# axiom_beta_sensor_cmv12000_v0_15_tht.net
KiCad netlist of a schematic drawn in EAGLE
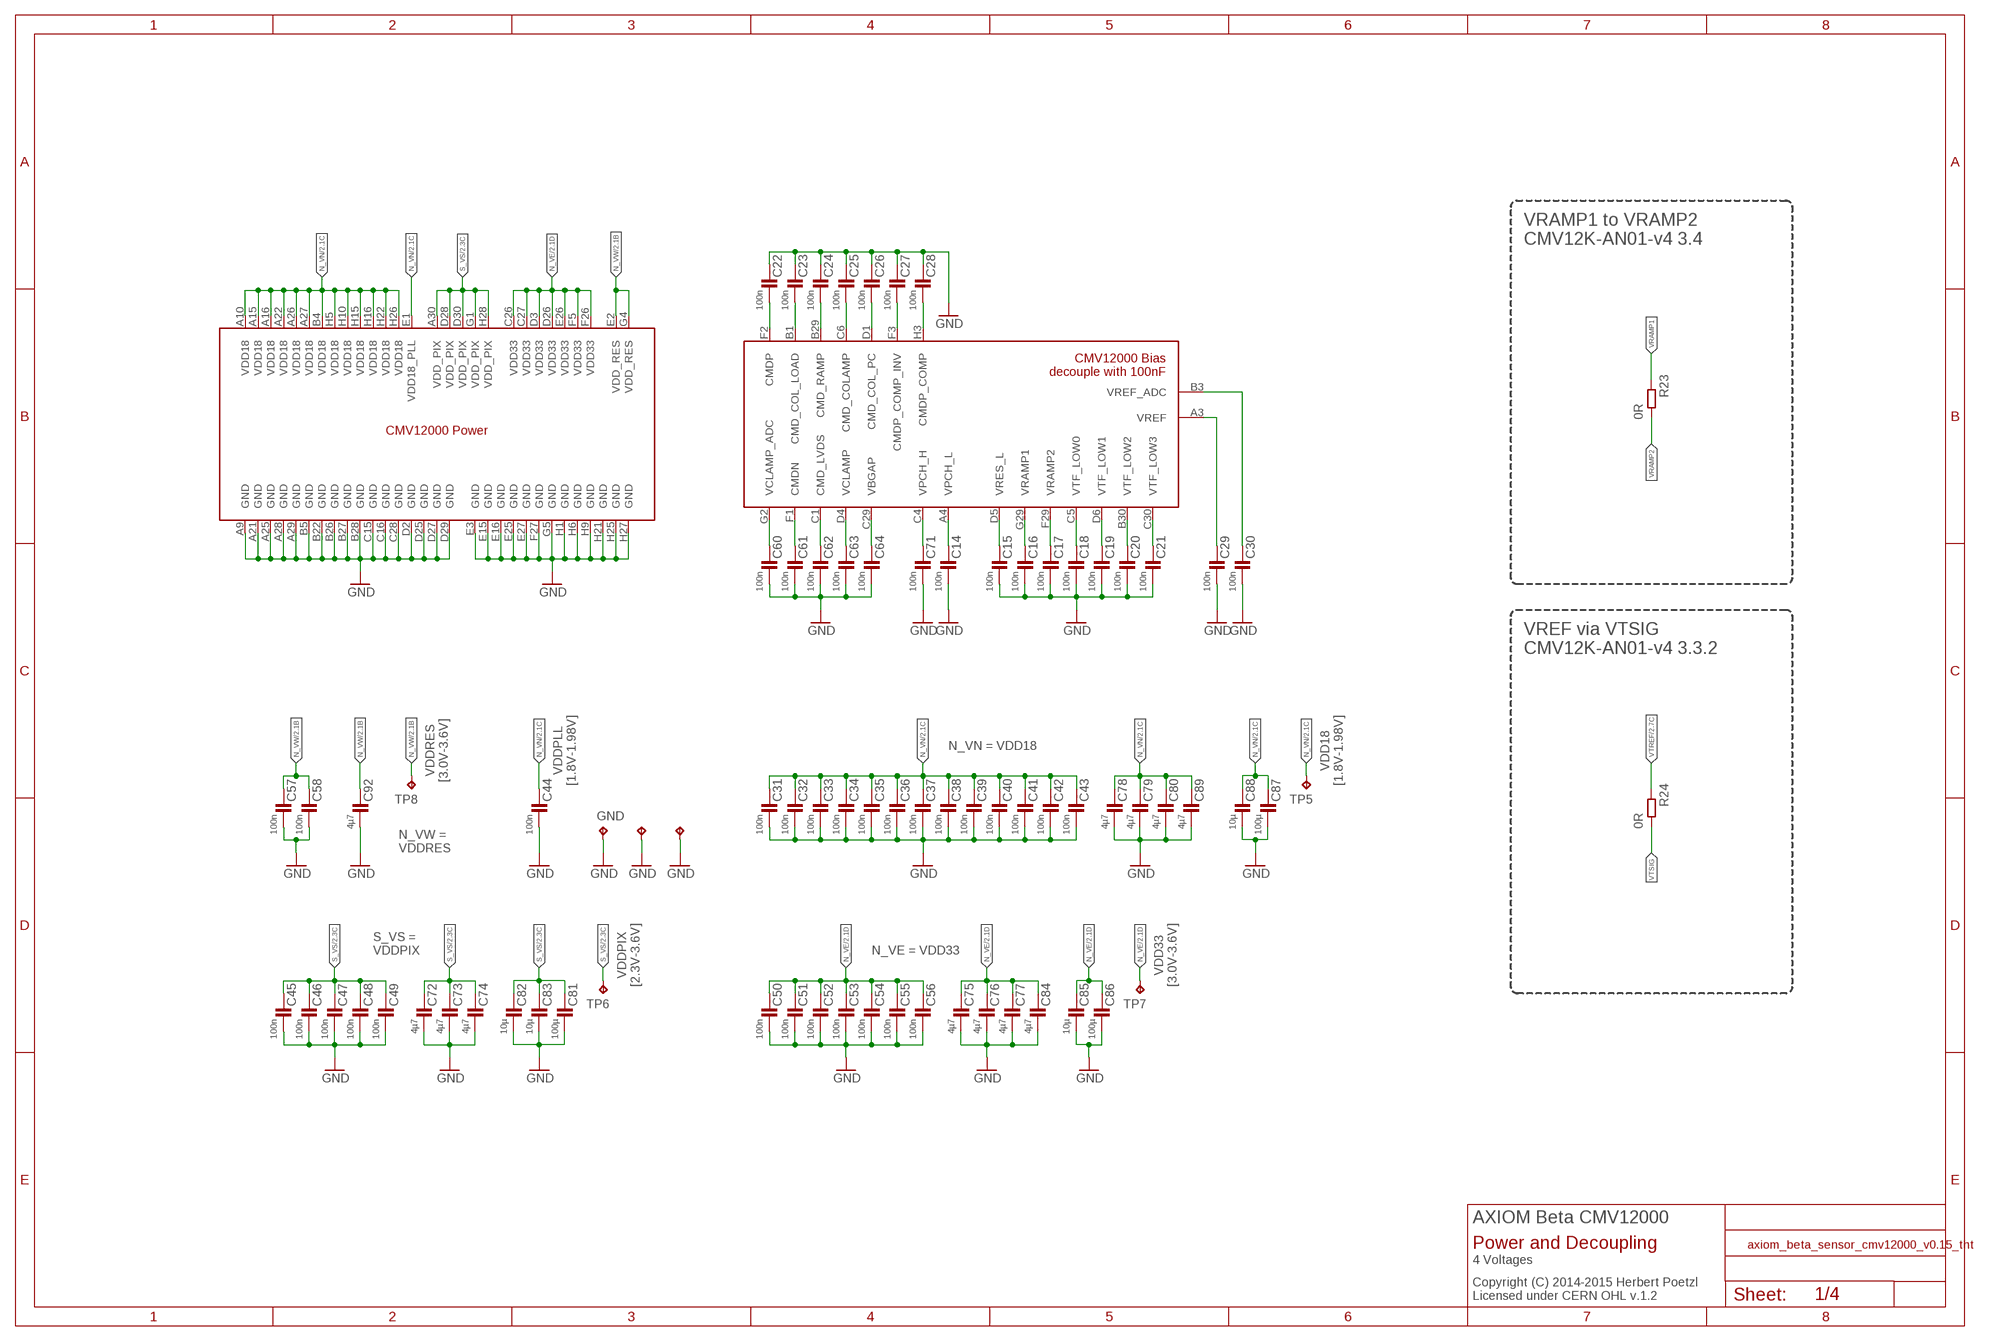
[diagram p0: schematic, sheet 1]
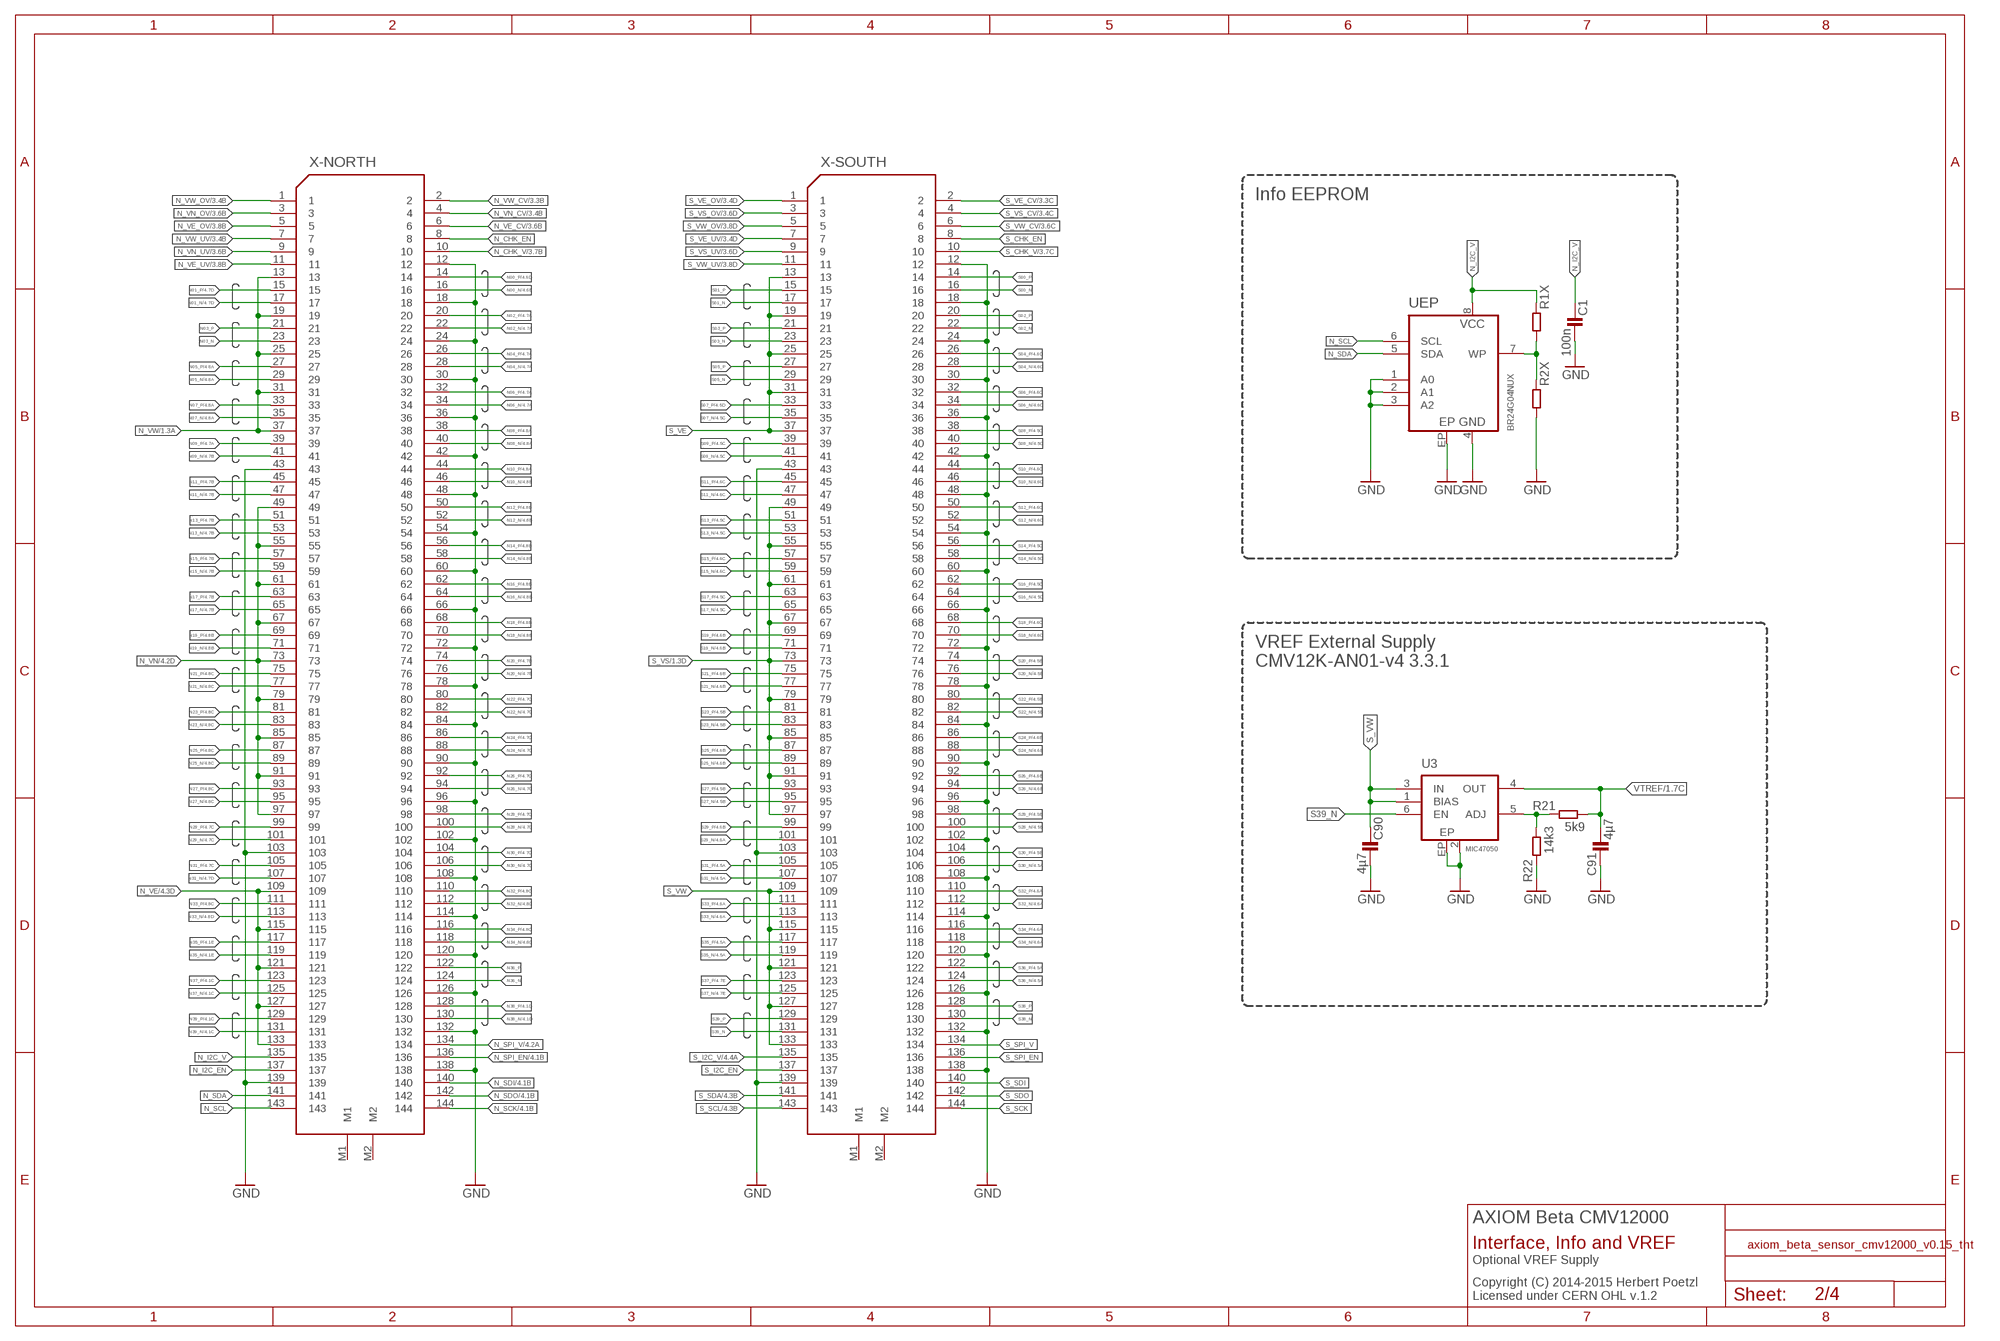
[diagram p1: schematic, sheet 2]
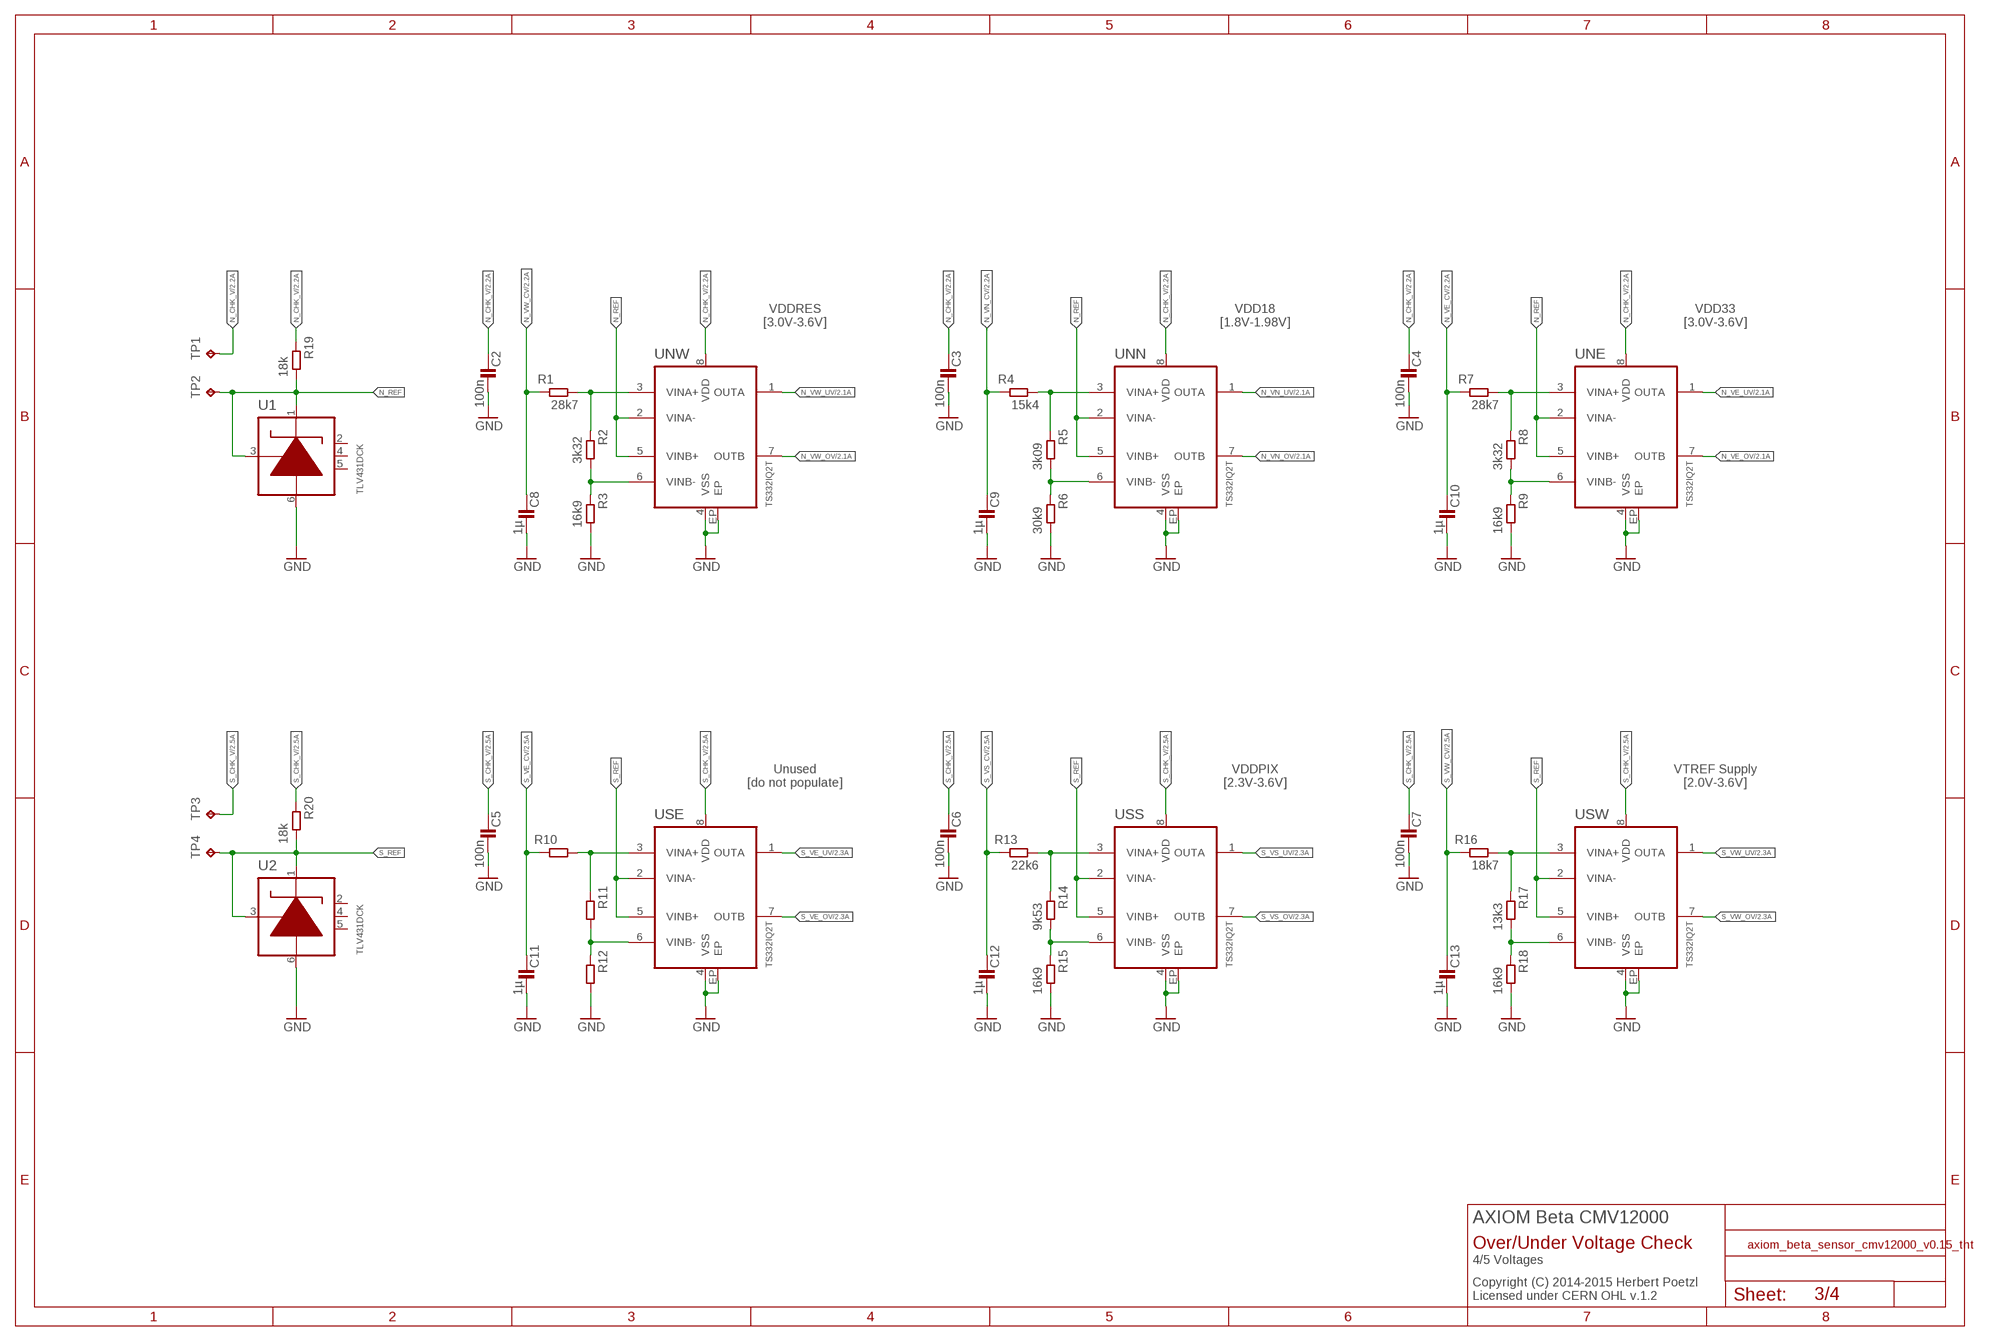
[diagram p2: schematic, sheet 3]
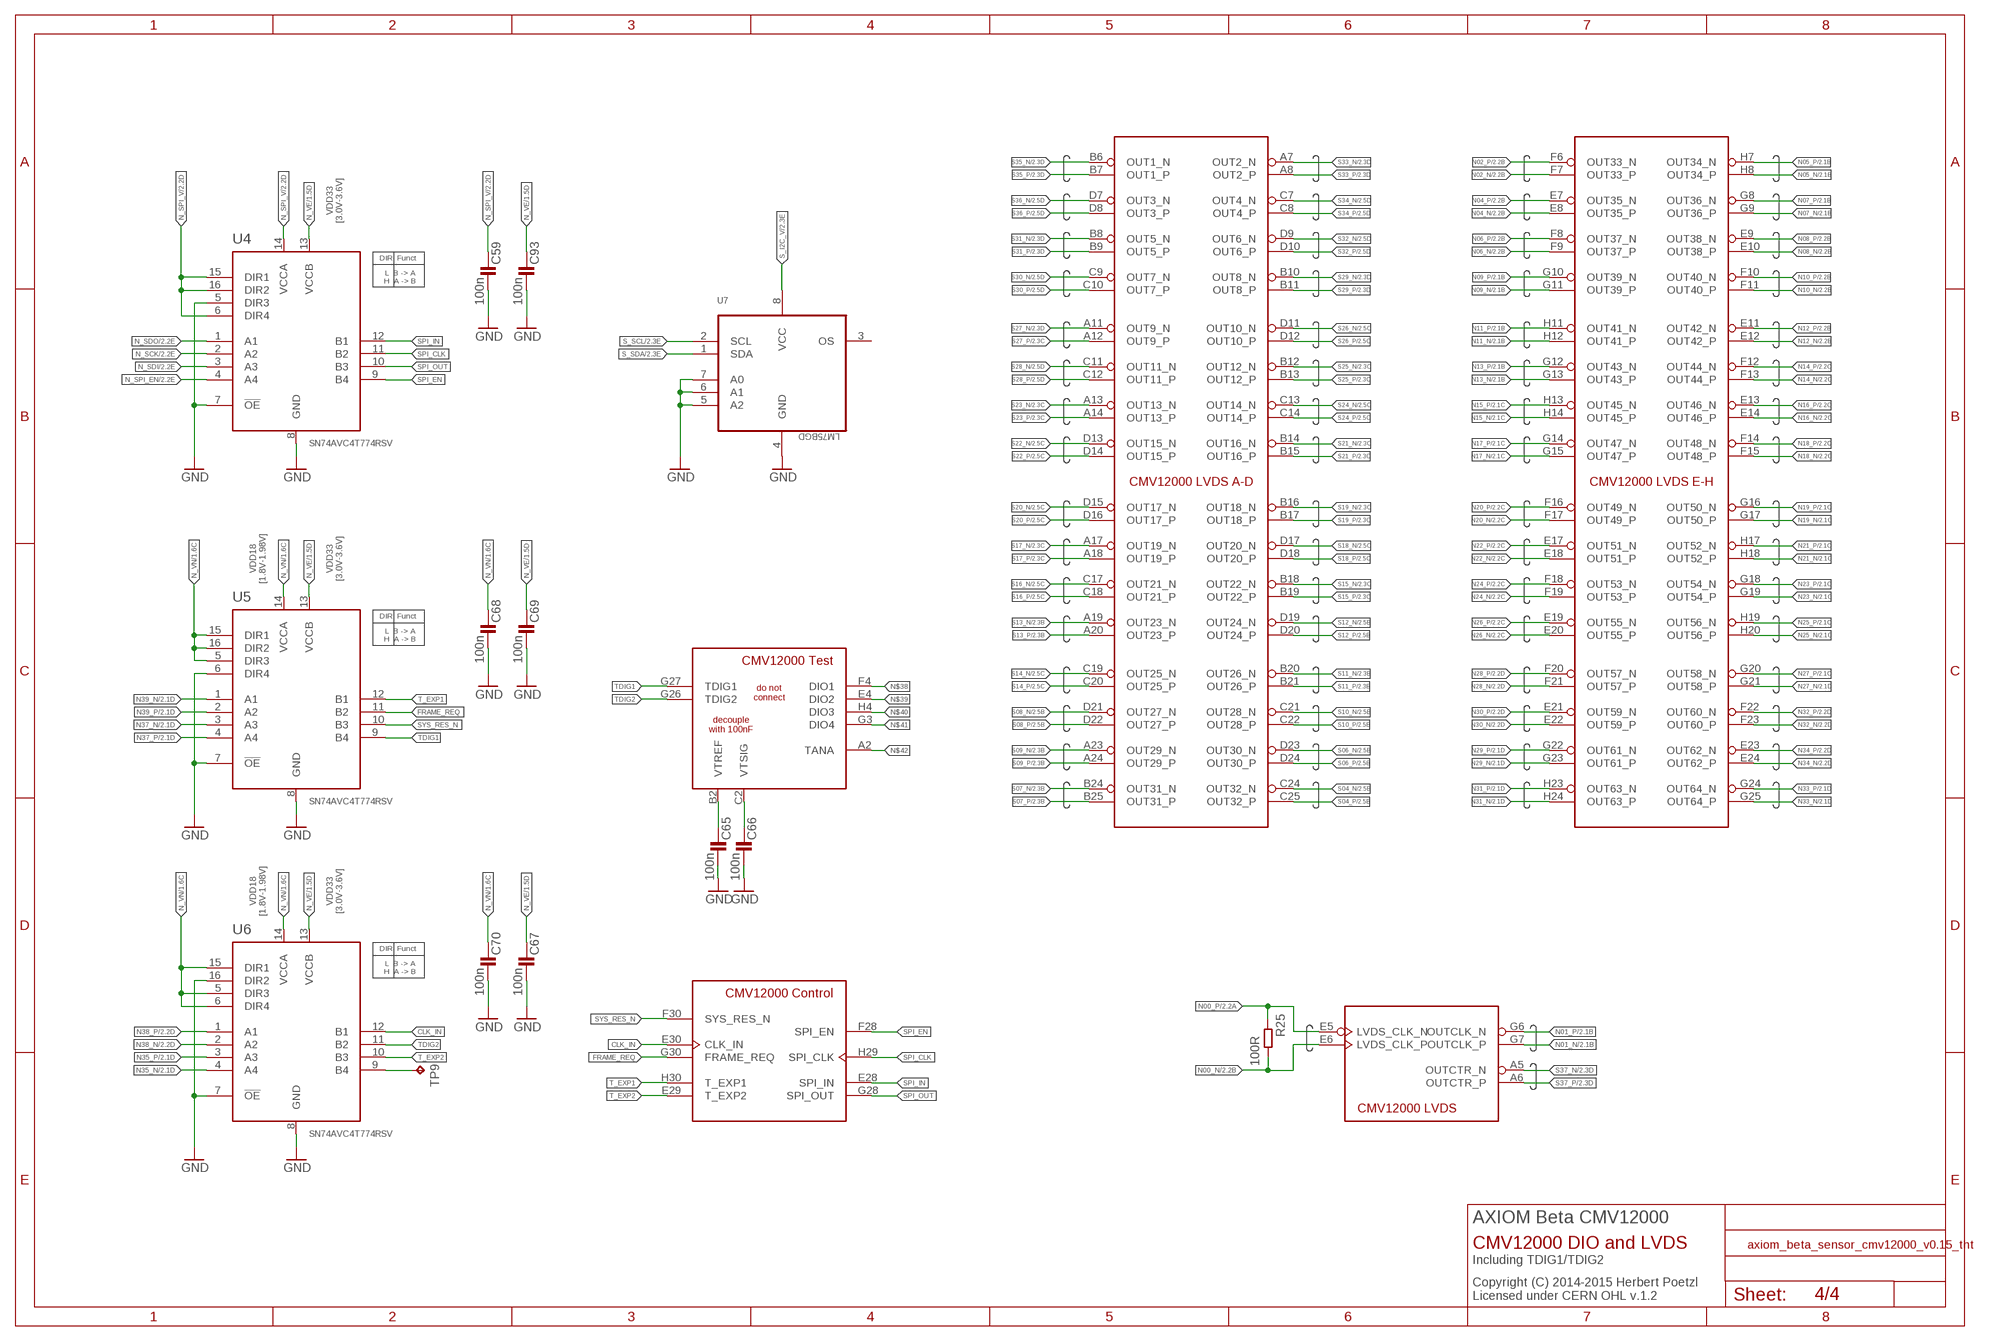
[diagram p3: schematic, sheet 4]

(export (version "E")
  (design (tool "Eeschema 10.0.6"))
  (components
    (comp (ref "C59")
      (value "100n")
      (footprint "eagle-import:0402-C")
      (libsource (lib "eagle-import") (part "C0402-C"))
    )
    (comp (ref "C65")
      (value "100n")
      (footprint "eagle-import:0402-C")
      (libsource (lib "eagle-import") (part "C0402-C"))
    )
    (comp (ref "C66")
      (value "100n")
      (footprint "eagle-import:0402-C")
      (libsource (lib "eagle-import") (part "C0402-C"))
    )
    (comp (ref "C67")
      (value "100n")
      (footprint "eagle-import:0402-C")
      (libsource (lib "eagle-import") (part "C0402-C"))
    )
    (comp (ref "C68")
      (value "100n")
      (footprint "eagle-import:0402-C")
      (libsource (lib "eagle-import") (part "C0402-C"))
    )
    (comp (ref "C69")
      (value "100n")
      (footprint "eagle-import:0402-C")
      (libsource (lib "eagle-import") (part "C0402-C"))
    )
    (comp (ref "C70")
      (value "100n")
      (footprint "eagle-import:0402-C")
      (libsource (lib "eagle-import") (part "C0402-C"))
    )
    (comp (ref "C93")
      (value "100n")
      (footprint "eagle-import:0402-C")
      (libsource (lib "eagle-import") (part "C0402-C"))
    )
    (comp (ref "R25")
      (value "100R")
      (footprint "eagle-import:0402-C")
      (libsource (lib "eagle-import") (part "R0402-C"))
    )
    (comp (ref "SENSOR")
      (value "CMV12000ANDON")
      (footprint "eagle-import:10-30-07-237-400T4")
      (libsource (lib "eagle-import") (part "CMV12000ANDON"))
    )
    (comp (ref "TP9")
      (value "TPTP10R")
      (footprint "eagle-import:TP10R")
      (libsource (lib "eagle-import") (part "TPTP10R"))
    )
    (comp (ref "U4")
      (value "SN74AVC4T774RSV")
      (footprint "eagle-import:QFN40P185X265X55-16N")
      (libsource (lib "eagle-import") (part "SN74AVC4T774RSV"))
    )
    (comp (ref "U5")
      (value "SN74AVC4T774RSV")
      (footprint "eagle-import:QFN40P185X265X55-16N")
      (libsource (lib "eagle-import") (part "SN74AVC4T774RSV"))
    )
    (comp (ref "U6")
      (value "SN74AVC4T774RSV")
      (footprint "eagle-import:QFN40P185X265X55-16N")
      (libsource (lib "eagle-import") (part "SN74AVC4T774RSV"))
    )
    (comp (ref "U7")
      (value "LM75BGD")
      (footprint "eagle-import:SOT996-2_3")
      (libsource (lib "eagle-import") (part "LM75BGD"))
    )
    (comp (ref "C1")
      (value "100n")
      (footprint "eagle-import:0402-C")
      (libsource (lib "eagle-import") (part "C0402-C"))
    )
    (comp (ref "C90")
      (value "4µ7")
      (footprint "eagle-import:0402-C")
      (libsource (lib "eagle-import") (part "C0402-C"))
    )
    (comp (ref "C91")
      (value "4µ7")
      (footprint "eagle-import:0402-C")
      (libsource (lib "eagle-import") (part "C0402-C"))
    )
    (comp (ref "R1X")
      (value "R0402-C")
      (footprint "eagle-import:0402-C")
      (libsource (lib "eagle-import") (part "R0402-C"))
    )
    (comp (ref "R2X")
      (value "R0402-C")
      (footprint "eagle-import:0402-C")
      (libsource (lib "eagle-import") (part "R0402-C"))
    )
    (comp (ref "R21")
      (value "5k9")
      (footprint "eagle-import:0402-C")
      (libsource (lib "eagle-import") (part "R0402-C"))
    )
    (comp (ref "R22")
      (value "14k3")
      (footprint "eagle-import:0402-C")
      (libsource (lib "eagle-import") (part "R0402-C"))
    )
    (comp (ref "U3")
      (value "MIC47050")
      (footprint "eagle-import:MLF-6")
      (libsource (lib "eagle-import") (part "MIC47050-ADJ"))
    )
    (comp (ref "UEP")
      (value "BR24G04NUX")
      (footprint "eagle-import:DFN200X300X100-9N")
      (libsource (lib "eagle-import") (part "BR24G04NUX"))
    )
    (comp (ref "X-NORTH")
      (value "FX10-144P")
      (footprint "eagle-import:FX10A-144P")
      (libsource (lib "eagle-import") (part "FX10-144P"))
    )
    (comp (ref "X-SOUTH")
      (value "FX10-144P")
      (footprint "eagle-import:FX10A-144P")
      (libsource (lib "eagle-import") (part "FX10-144P"))
    )
    (comp (ref "C2")
      (value "100n")
      (footprint "eagle-import:0402-C")
      (libsource (lib "eagle-import") (part "C0402-C"))
    )
    (comp (ref "C3")
      (value "100n")
      (footprint "eagle-import:0402-C")
      (libsource (lib "eagle-import") (part "C0402-C"))
    )
    (comp (ref "C4")
      (value "100n")
      (footprint "eagle-import:0402-C")
      (libsource (lib "eagle-import") (part "C0402-C"))
    )
    (comp (ref "C5")
      (value "100n")
      (footprint "eagle-import:0402-C")
      (libsource (lib "eagle-import") (part "C0402-C"))
    )
    (comp (ref "C6")
      (value "100n")
      (footprint "eagle-import:0402-C")
      (libsource (lib "eagle-import") (part "C0402-C"))
    )
    (comp (ref "C7")
      (value "100n")
      (footprint "eagle-import:0402-C")
      (libsource (lib "eagle-import") (part "C0402-C"))
    )
    (comp (ref "C8")
      (value "1µ")
      (footprint "eagle-import:0402-C")
      (libsource (lib "eagle-import") (part "C0402-C"))
    )
    (comp (ref "C9")
      (value "1µ")
      (footprint "eagle-import:0402-C")
      (libsource (lib "eagle-import") (part "C0402-C"))
    )
    (comp (ref "C10")
      (value "1µ")
      (footprint "eagle-import:0402-C")
      (libsource (lib "eagle-import") (part "C0402-C"))
    )
    (comp (ref "C11")
      (value "1µ")
      (footprint "eagle-import:0402-C")
      (libsource (lib "eagle-import") (part "C0402-C"))
    )
    (comp (ref "C12")
      (value "1µ")
      (footprint "eagle-import:0402-C")
      (libsource (lib "eagle-import") (part "C0402-C"))
    )
    (comp (ref "C13")
      (value "1µ")
      (footprint "eagle-import:0402-C")
      (libsource (lib "eagle-import") (part "C0402-C"))
    )
    (comp (ref "R1")
      (value "28k7")
      (footprint "eagle-import:0402-C")
      (libsource (lib "eagle-import") (part "R0402-C"))
    )
    (comp (ref "R2")
      (value "3k32")
      (footprint "eagle-import:0402-C")
      (libsource (lib "eagle-import") (part "R0402-C"))
    )
    (comp (ref "R3")
      (value "16k9")
      (footprint "eagle-import:0402-C")
      (libsource (lib "eagle-import") (part "R0402-C"))
    )
    (comp (ref "R4")
      (value "15k4")
      (footprint "eagle-import:0402-C")
      (libsource (lib "eagle-import") (part "R0402-C"))
    )
    (comp (ref "R5")
      (value "3k09")
      (footprint "eagle-import:0402-C")
      (libsource (lib "eagle-import") (part "R0402-C"))
    )
    (comp (ref "R6")
      (value "30k9")
      (footprint "eagle-import:0402-C")
      (libsource (lib "eagle-import") (part "R0402-C"))
    )
    (comp (ref "R7")
      (value "28k7")
      (footprint "eagle-import:0402-C")
      (libsource (lib "eagle-import") (part "R0402-C"))
    )
    (comp (ref "R8")
      (value "3k32")
      (footprint "eagle-import:0402-C")
      (libsource (lib "eagle-import") (part "R0402-C"))
    )
    (comp (ref "R9")
      (value "16k9")
      (footprint "eagle-import:0402-C")
      (libsource (lib "eagle-import") (part "R0402-C"))
    )
    (comp (ref "R10")
      (value "R0402-C")
      (footprint "eagle-import:0402-C")
      (libsource (lib "eagle-import") (part "R0402-C"))
    )
    (comp (ref "R11")
      (value "R0402-C")
      (footprint "eagle-import:0402-C")
      (libsource (lib "eagle-import") (part "R0402-C"))
    )
    (comp (ref "R12")
      (value "R0402-C")
      (footprint "eagle-import:0402-C")
      (libsource (lib "eagle-import") (part "R0402-C"))
    )
    (comp (ref "R13")
      (value "22k6")
      (footprint "eagle-import:0402-C")
      (libsource (lib "eagle-import") (part "R0402-C"))
    )
    (comp (ref "R14")
      (value "9k53")
      (footprint "eagle-import:0402-C")
      (libsource (lib "eagle-import") (part "R0402-C"))
    )
    (comp (ref "R15")
      (value "16k9")
      (footprint "eagle-import:0402-C")
      (libsource (lib "eagle-import") (part "R0402-C"))
    )
    (comp (ref "R16")
      (value "18k7")
      (footprint "eagle-import:0402-C")
      (libsource (lib "eagle-import") (part "R0402-C"))
    )
    (comp (ref "R17")
      (value "13k3")
      (footprint "eagle-import:0402-C")
      (libsource (lib "eagle-import") (part "R0402-C"))
    )
    (comp (ref "R18")
      (value "16k9")
      (footprint "eagle-import:0402-C")
      (libsource (lib "eagle-import") (part "R0402-C"))
    )
    (comp (ref "R19")
      (value "18k")
      (footprint "eagle-import:0402-C")
      (libsource (lib "eagle-import") (part "R0402-C"))
    )
    (comp (ref "R20")
      (value "18k")
      (footprint "eagle-import:0402-C")
      (libsource (lib "eagle-import") (part "R0402-C"))
    )
    (comp (ref "TP1")
      (value "TPTP10R")
      (footprint "eagle-import:TP10R")
      (libsource (lib "eagle-import") (part "TPTP10R"))
    )
    (comp (ref "TP2")
      (value "TPTP10R")
      (footprint "eagle-import:TP10R")
      (libsource (lib "eagle-import") (part "TPTP10R"))
    )
    (comp (ref "TP3")
      (value "TPTP10R")
      (footprint "eagle-import:TP10R")
      (libsource (lib "eagle-import") (part "TPTP10R"))
    )
    (comp (ref "TP4")
      (value "TPTP10R")
      (footprint "eagle-import:TP10R")
      (libsource (lib "eagle-import") (part "TPTP10R"))
    )
    (comp (ref "U1")
      (value "TLV431DCK")
      (footprint "eagle-import:SOT65P210X110-6N")
      (libsource (lib "eagle-import") (part "TLV431DCK"))
    )
    (comp (ref "U2")
      (value "TLV431DCK")
      (footprint "eagle-import:SOT65P210X110-6N")
      (libsource (lib "eagle-import") (part "TLV431DCK"))
    )
    (comp (ref "UNE")
      (value "TS332IQ2T")
      (footprint "eagle-import:DFN200X200X100-9N")
      (libsource (lib "eagle-import") (part "TS332IQ2T"))
    )
    (comp (ref "UNN")
      (value "TS332IQ2T")
      (footprint "eagle-import:DFN200X200X100-9N")
      (libsource (lib "eagle-import") (part "TS332IQ2T"))
    )
    (comp (ref "UNW")
      (value "TS332IQ2T")
      (footprint "eagle-import:DFN200X200X100-9N")
      (libsource (lib "eagle-import") (part "TS332IQ2T"))
    )
    (comp (ref "USE")
      (value "TS332IQ2T")
      (footprint "eagle-import:DFN200X200X100-9N")
      (libsource (lib "eagle-import") (part "TS332IQ2T"))
    )
    (comp (ref "USS")
      (value "TS332IQ2T")
      (footprint "eagle-import:DFN200X200X100-9N")
      (libsource (lib "eagle-import") (part "TS332IQ2T"))
    )
    (comp (ref "USW")
      (value "TS332IQ2T")
      (footprint "eagle-import:DFN200X200X100-9N")
      (libsource (lib "eagle-import") (part "TS332IQ2T"))
    )
    (comp (ref "C14")
      (value "100n")
      (footprint "eagle-import:0402-C")
      (libsource (lib "eagle-import") (part "C0402-C"))
    )
    (comp (ref "C15")
      (value "100n")
      (footprint "eagle-import:0402-C")
      (libsource (lib "eagle-import") (part "C0402-C"))
    )
    (comp (ref "C16")
      (value "100n")
      (footprint "eagle-import:0402-C")
      (libsource (lib "eagle-import") (part "C0402-C"))
    )
    (comp (ref "C17")
      (value "100n")
      (footprint "eagle-import:0402-C")
      (libsource (lib "eagle-import") (part "C0402-C"))
    )
    (comp (ref "C18")
      (value "100n")
      (footprint "eagle-import:0402-C")
      (libsource (lib "eagle-import") (part "C0402-C"))
    )
    (comp (ref "C19")
      (value "100n")
      (footprint "eagle-import:0402-C")
      (libsource (lib "eagle-import") (part "C0402-C"))
    )
    (comp (ref "C20")
      (value "100n")
      (footprint "eagle-import:0402-C")
      (libsource (lib "eagle-import") (part "C0402-C"))
    )
    (comp (ref "C21")
      (value "100n")
      (footprint "eagle-import:0402-C")
      (libsource (lib "eagle-import") (part "C0402-C"))
    )
    (comp (ref "C22")
      (value "100n")
      (footprint "eagle-import:0402-C")
      (libsource (lib "eagle-import") (part "C0402-C"))
    )
    (comp (ref "C23")
      (value "100n")
      (footprint "eagle-import:0402-C")
      (libsource (lib "eagle-import") (part "C0402-C"))
    )
    (comp (ref "C24")
      (value "100n")
      (footprint "eagle-import:0402-C")
      (libsource (lib "eagle-import") (part "C0402-C"))
    )
    (comp (ref "C25")
      (value "100n")
      (footprint "eagle-import:0402-C")
      (libsource (lib "eagle-import") (part "C0402-C"))
    )
    (comp (ref "C26")
      (value "100n")
      (footprint "eagle-import:0402-C")
      (libsource (lib "eagle-import") (part "C0402-C"))
    )
    (comp (ref "C27")
      (value "100n")
      (footprint "eagle-import:0402-C")
      (libsource (lib "eagle-import") (part "C0402-C"))
    )
    (comp (ref "C28")
      (value "100n")
      (footprint "eagle-import:0402-C")
      (libsource (lib "eagle-import") (part "C0402-C"))
    )
    (comp (ref "C29")
      (value "100n")
      (footprint "eagle-import:0402-C")
      (libsource (lib "eagle-import") (part "C0402-C"))
    )
    (comp (ref "C30")
      (value "100n")
      (footprint "eagle-import:0402-C")
      (libsource (lib "eagle-import") (part "C0402-C"))
    )
    (comp (ref "C31")
      (value "100n")
      (footprint "eagle-import:0402-C")
      (libsource (lib "eagle-import") (part "C0402-C"))
    )
    (comp (ref "C32")
      (value "100n")
      (footprint "eagle-import:0402-C")
      (libsource (lib "eagle-import") (part "C0402-C"))
    )
    (comp (ref "C33")
      (value "100n")
      (footprint "eagle-import:0402-C")
      (libsource (lib "eagle-import") (part "C0402-C"))
    )
    (comp (ref "C34")
      (value "100n")
      (footprint "eagle-import:0402-C")
      (libsource (lib "eagle-import") (part "C0402-C"))
    )
    (comp (ref "C35")
      (value "100n")
      (footprint "eagle-import:0402-C")
      (libsource (lib "eagle-import") (part "C0402-C"))
    )
    (comp (ref "C36")
      (value "100n")
      (footprint "eagle-import:0402-C")
      (libsource (lib "eagle-import") (part "C0402-C"))
    )
    (comp (ref "C37")
      (value "100n")
      (footprint "eagle-import:0402-C")
      (libsource (lib "eagle-import") (part "C0402-C"))
    )
    (comp (ref "C38")
      (value "100n")
      (footprint "eagle-import:0402-C")
      (libsource (lib "eagle-import") (part "C0402-C"))
    )
    (comp (ref "C39")
      (value "100n")
      (footprint "eagle-import:0402-C")
      (libsource (lib "eagle-import") (part "C0402-C"))
    )
    (comp (ref "C40")
      (value "100n")
      (footprint "eagle-import:0402-C")
      (libsource (lib "eagle-import") (part "C0402-C"))
    )
    (comp (ref "C41")
      (value "100n")
      (footprint "eagle-import:0402-C")
      (libsource (lib "eagle-import") (part "C0402-C"))
    )
    (comp (ref "C42")
      (value "100n")
      (footprint "eagle-import:0402-C")
      (libsource (lib "eagle-import") (part "C0402-C"))
    )
    (comp (ref "C43")
      (value "100n")
      (footprint "eagle-import:0402-C")
      (libsource (lib "eagle-import") (part "C0402-C"))
    )
    (comp (ref "C44")
      (value "100n")
      (footprint "eagle-import:0402-C")
      (libsource (lib "eagle-import") (part "C0402-C"))
    )
    (comp (ref "C45")
      (value "100n")
      (footprint "eagle-import:0402-C")
      (libsource (lib "eagle-import") (part "C0402-C"))
    )
    (comp (ref "C46")
      (value "100n")
      (footprint "eagle-import:0402-C")
      (libsource (lib "eagle-import") (part "C0402-C"))
    )
    (comp (ref "C47")
      (value "100n")
      (footprint "eagle-import:0402-C")
      (libsource (lib "eagle-import") (part "C0402-C"))
    )
    (comp (ref "C48")
      (value "100n")
      (footprint "eagle-import:0402-C")
      (libsource (lib "eagle-import") (part "C0402-C"))
    )
    (comp (ref "C49")
      (value "100n")
      (footprint "eagle-import:0402-C")
      (libsource (lib "eagle-import") (part "C0402-C"))
    )
    (comp (ref "C50")
      (value "100n")
      (footprint "eagle-import:0402-C")
      (libsource (lib "eagle-import") (part "C0402-C"))
    )
    (comp (ref "C51")
      (value "100n")
      (footprint "eagle-import:0402-C")
      (libsource (lib "eagle-import") (part "C0402-C"))
    )
    (comp (ref "C52")
      (value "100n")
      (footprint "eagle-import:0402-C")
      (libsource (lib "eagle-import") (part "C0402-C"))
    )
    (comp (ref "C53")
      (value "100n")
      (footprint "eagle-import:0402-C")
      (libsource (lib "eagle-import") (part "C0402-C"))
    )
    (comp (ref "C54")
      (value "100n")
      (footprint "eagle-import:0402-C")
      (libsource (lib "eagle-import") (part "C0402-C"))
    )
    (comp (ref "C55")
      (value "100n")
      (footprint "eagle-import:0402-C")
      (libsource (lib "eagle-import") (part "C0402-C"))
    )
    (comp (ref "C56")
      (value "100n")
      (footprint "eagle-import:0402-C")
      (libsource (lib "eagle-import") (part "C0402-C"))
    )
    (comp (ref "C57")
      (value "100n")
      (footprint "eagle-import:0402-C")
      (libsource (lib "eagle-import") (part "C0402-C"))
    )
    (comp (ref "C58")
      (value "100n")
      (footprint "eagle-import:0402-C")
      (libsource (lib "eagle-import") (part "C0402-C"))
    )
    (comp (ref "C60")
      (value "100n")
      (footprint "eagle-import:0402-C")
      (libsource (lib "eagle-import") (part "C0402-C"))
    )
    (comp (ref "C61")
      (value "100n")
      (footprint "eagle-import:0402-C")
      (libsource (lib "eagle-import") (part "C0402-C"))
    )
    (comp (ref "C62")
      (value "100n")
      (footprint "eagle-import:0402-C")
      (libsource (lib "eagle-import") (part "C0402-C"))
    )
    (comp (ref "C63")
      (value "100n")
      (footprint "eagle-import:0402-C")
      (libsource (lib "eagle-import") (part "C0402-C"))
    )
    (comp (ref "C64")
      (value "100n")
      (footprint "eagle-import:0402-C")
      (libsource (lib "eagle-import") (part "C0402-C"))
    )
    (comp (ref "C71")
      (value "100n")
      (footprint "eagle-import:0402-C")
      (libsource (lib "eagle-import") (part "C0402-C"))
    )
    (comp (ref "C72")
      (value "4µ7")
      (footprint "eagle-import:0402-B")
      (libsource (lib "eagle-import") (part "C0402-B"))
    )
    (comp (ref "C73")
      (value "4µ7")
      (footprint "eagle-import:0402-C")
      (libsource (lib "eagle-import") (part "C0402-C"))
    )
    (comp (ref "C74")
      (value "4µ7")
      (footprint "eagle-import:0402-C")
      (libsource (lib "eagle-import") (part "C0402-C"))
    )
    (comp (ref "C75")
      (value "4µ7")
      (footprint "eagle-import:0402-C")
      (libsource (lib "eagle-import") (part "C0402-C"))
    )
    (comp (ref "C76")
      (value "4µ7")
      (footprint "eagle-import:0402-C")
      (libsource (lib "eagle-import") (part "C0402-C"))
    )
    (comp (ref "C77")
      (value "4µ7")
      (footprint "eagle-import:0402-B")
      (libsource (lib "eagle-import") (part "C0402-B"))
    )
    (comp (ref "C78")
      (value "4µ7")
      (footprint "eagle-import:0402-B")
      (libsource (lib "eagle-import") (part "C0402-B"))
    )
    (comp (ref "C79")
      (value "4µ7")
      (footprint "eagle-import:0402-C")
      (libsource (lib "eagle-import") (part "C0402-C"))
    )
    (comp (ref "C80")
      (value "4µ7")
      (footprint "eagle-import:0402-C")
      (libsource (lib "eagle-import") (part "C0402-C"))
    )
    (comp (ref "C81")
      (value "100µ")
      (footprint "eagle-import:1206-B")
      (libsource (lib "eagle-import") (part "C1206-B"))
    )
    (comp (ref "C82")
      (value "10µ")
      (footprint "eagle-import:0603-C")
      (libsource (lib "eagle-import") (part "C0603-C"))
    )
    (comp (ref "C83")
      (value "10µ")
      (footprint "eagle-import:0603-C")
      (libsource (lib "eagle-import") (part "C0603-C"))
    )
    (comp (ref "C84")
      (value "4µ7")
      (footprint "eagle-import:0402-C")
      (libsource (lib "eagle-import") (part "C0402-C"))
    )
    (comp (ref "C85")
      (value "10µ")
      (footprint "eagle-import:0603-C")
      (libsource (lib "eagle-import") (part "C0603-C"))
    )
    (comp (ref "C86")
      (value "100µ")
      (footprint "eagle-import:1206-B")
      (libsource (lib "eagle-import") (part "C1206-B"))
    )
    (comp (ref "C87")
      (value "100µ")
      (footprint "eagle-import:1206-B")
      (libsource (lib "eagle-import") (part "C1206-B"))
    )
    (comp (ref "C88")
      (value "10µ")
      (footprint "eagle-import:0603-C")
      (libsource (lib "eagle-import") (part "C0603-C"))
    )
    (comp (ref "C89")
      (value "4µ7")
      (footprint "eagle-import:0402-C")
      (libsource (lib "eagle-import") (part "C0402-C"))
    )
    (comp (ref "C92")
      (value "4µ7")
      (footprint "eagle-import:0402-C")
      (libsource (lib "eagle-import") (part "C0402-C"))
    )
    (comp (ref "GND")
      (value "TPTP10R")
      (footprint "eagle-import:TP10R")
      (libsource (lib "eagle-import") (part "TPTP10R"))
    )
    (comp (ref "GND75")
      (value "TPTP10R")
      (footprint "eagle-import:TP10R")
      (libsource (lib "eagle-import") (part "TPTP10R"))
    )
    (comp (ref "GND77")
      (value "TPTP10R")
      (footprint "eagle-import:TP10R")
      (libsource (lib "eagle-import") (part "TPTP10R"))
    )
    (comp (ref "R23")
      (value "0R")
      (footprint "eagle-import:0402-C")
      (libsource (lib "eagle-import") (part "R0402-C"))
    )
    (comp (ref "R24")
      (value "0R")
      (footprint "eagle-import:0402-C")
      (libsource (lib "eagle-import") (part "R0402-C"))
    )
    (comp (ref "TP5")
      (value "TPTP10R")
      (footprint "eagle-import:TP10R")
      (libsource (lib "eagle-import") (part "TPTP10R"))
    )
    (comp (ref "TP6")
      (value "TPTP10R")
      (footprint "eagle-import:TP10R")
      (libsource (lib "eagle-import") (part "TPTP10R"))
    )
    (comp (ref "TP7")
      (value "TPTP10R")
      (footprint "eagle-import:TP10R")
      (libsource (lib "eagle-import") (part "TPTP10R"))
    )
    (comp (ref "TP8")
      (value "TPTP10R")
      (footprint "eagle-import:TP10R")
      (libsource (lib "eagle-import") (part "TPTP10R"))
    )
  )
  (nets
    (net (code "1") (name "CLK_IN") (class "Default")
      (node (ref "SENSOR") (pin "E30") (pinfunction "CLK_IN_E30") (pintype "input"))
      (node (ref "U6") (pin "12") (pinfunction "B1_12") (pintype "bidirectional"))
    )
    (net (code "2") (name "FRAME_REQ") (class "Default")
      (node (ref "SENSOR") (pin "G30") (pinfunction "FRAME_REQ_G30") (pintype "input"))
      (node (ref "U5") (pin "11") (pinfunction "B2_11") (pintype "bidirectional"))
    )
    (net (code "3") (name "GND") (class "Default")
      (node (ref "C1") (pin "2") (pinfunction "2_2") (pintype "passive"))
      (node (ref "C10") (pin "2") (pinfunction "2_2") (pintype "passive"))
      (node (ref "C11") (pin "2") (pinfunction "2_2") (pintype "passive"))
      (node (ref "C12") (pin "2") (pinfunction "2_2") (pintype "passive"))
      (node (ref "C13") (pin "2") (pinfunction "2_2") (pintype "passive"))
      (node (ref "C14") (pin "2") (pinfunction "2_2") (pintype "passive"))
      (node (ref "C15") (pin "2") (pinfunction "2_2") (pintype "passive"))
      (node (ref "C16") (pin "2") (pinfunction "2_2") (pintype "passive"))
      (node (ref "C17") (pin "2") (pinfunction "2_2") (pintype "passive"))
      (node (ref "C18") (pin "2") (pinfunction "2_2") (pintype "passive"))
      (node (ref "C19") (pin "2") (pinfunction "2_2") (pintype "passive"))
      (node (ref "C2") (pin "2") (pinfunction "2_2") (pintype "passive"))
      (node (ref "C20") (pin "2") (pinfunction "2_2") (pintype "passive"))
      (node (ref "C21") (pin "2") (pinfunction "2_2") (pintype "passive"))
      (node (ref "C22") (pin "1") (pinfunction "1_1") (pintype "passive"))
      (node (ref "C23") (pin "1") (pinfunction "1_1") (pintype "passive"))
      (node (ref "C24") (pin "1") (pinfunction "1_1") (pintype "passive"))
      (node (ref "C25") (pin "1") (pinfunction "1_1") (pintype "passive"))
      (node (ref "C26") (pin "1") (pinfunction "1_1") (pintype "passive"))
      (node (ref "C27") (pin "1") (pinfunction "1_1") (pintype "passive"))
      (node (ref "C28") (pin "1") (pinfunction "1_1") (pintype "passive"))
      (node (ref "C29") (pin "2") (pinfunction "2_2") (pintype "passive"))
      (node (ref "C3") (pin "2") (pinfunction "2_2") (pintype "passive"))
      (node (ref "C30") (pin "2") (pinfunction "2_2") (pintype "passive"))
      (node (ref "C31") (pin "2") (pinfunction "2_2") (pintype "passive"))
      (node (ref "C32") (pin "2") (pinfunction "2_2") (pintype "passive"))
      (node (ref "C33") (pin "2") (pinfunction "2_2") (pintype "passive"))
      (node (ref "C34") (pin "2") (pinfunction "2_2") (pintype "passive"))
      (node (ref "C35") (pin "2") (pinfunction "2_2") (pintype "passive"))
      (node (ref "C36") (pin "2") (pinfunction "2_2") (pintype "passive"))
      (node (ref "C37") (pin "2") (pinfunction "2_2") (pintype "passive"))
      (node (ref "C38") (pin "2") (pinfunction "2_2") (pintype "passive"))
      (node (ref "C39") (pin "2") (pinfunction "2_2") (pintype "passive"))
      (node (ref "C4") (pin "2") (pinfunction "2_2") (pintype "passive"))
      (node (ref "C40") (pin "2") (pinfunction "2_2") (pintype "passive"))
      (node (ref "C41") (pin "2") (pinfunction "2_2") (pintype "passive"))
      (node (ref "C42") (pin "2") (pinfunction "2_2") (pintype "passive"))
      (node (ref "C43") (pin "2") (pinfunction "2_2") (pintype "passive"))
      (node (ref "C44") (pin "2") (pinfunction "2_2") (pintype "passive"))
      (node (ref "C45") (pin "2") (pinfunction "2_2") (pintype "passive"))
      (node (ref "C46") (pin "2") (pinfunction "2_2") (pintype "passive"))
      (node (ref "C47") (pin "2") (pinfunction "2_2") (pintype "passive"))
      (node (ref "C48") (pin "2") (pinfunction "2_2") (pintype "passive"))
      (node (ref "C49") (pin "2") (pinfunction "2_2") (pintype "passive"))
      (node (ref "C5") (pin "2") (pinfunction "2_2") (pintype "passive"))
      (node (ref "C50") (pin "2") (pinfunction "2_2") (pintype "passive"))
      (node (ref "C51") (pin "2") (pinfunction "2_2") (pintype "passive"))
      (node (ref "C52") (pin "2") (pinfunction "2_2") (pintype "passive"))
      (node (ref "C53") (pin "2") (pinfunction "2_2") (pintype "passive"))
      (node (ref "C54") (pin "2") (pinfunction "2_2") (pintype "passive"))
      (node (ref "C55") (pin "2") (pinfunction "2_2") (pintype "passive"))
      (node (ref "C56") (pin "2") (pinfunction "2_2") (pintype "passive"))
      (node (ref "C57") (pin "2") (pinfunction "2_2") (pintype "passive"))
      (node (ref "C58") (pin "2") (pinfunction "2_2") (pintype "passive"))
      (node (ref "C59") (pin "2") (pinfunction "2_2") (pintype "passive"))
      (node (ref "C6") (pin "2") (pinfunction "2_2") (pintype "passive"))
      (node (ref "C60") (pin "2") (pinfunction "2_2") (pintype "passive"))
      (node (ref "C61") (pin "2") (pinfunction "2_2") (pintype "passive"))
      (node (ref "C62") (pin "2") (pinfunction "2_2") (pintype "passive"))
      (node (ref "C63") (pin "2") (pinfunction "2_2") (pintype "passive"))
      (node (ref "C64") (pin "2") (pinfunction "2_2") (pintype "passive"))
      (node (ref "C65") (pin "2") (pinfunction "2_2") (pintype "passive"))
      (node (ref "C66") (pin "2") (pinfunction "2_2") (pintype "passive"))
      (node (ref "C67") (pin "2") (pinfunction "2_2") (pintype "passive"))
      (node (ref "C68") (pin "2") (pinfunction "2_2") (pintype "passive"))
      (node (ref "C69") (pin "2") (pinfunction "2_2") (pintype "passive"))
      (node (ref "C7") (pin "2") (pinfunction "2_2") (pintype "passive"))
      (node (ref "C70") (pin "2") (pinfunction "2_2") (pintype "passive"))
      (node (ref "C71") (pin "2") (pinfunction "2_2") (pintype "passive"))
      (node (ref "C72") (pin "2") (pinfunction "2_2") (pintype "passive"))
      (node (ref "C73") (pin "2") (pinfunction "2_2") (pintype "passive"))
      (node (ref "C74") (pin "2") (pinfunction "2_2") (pintype "passive"))
      (node (ref "C75") (pin "2") (pinfunction "2_2") (pintype "passive"))
      (node (ref "C76") (pin "2") (pinfunction "2_2") (pintype "passive"))
      (node (ref "C77") (pin "2") (pinfunction "2_2") (pintype "passive"))
      (node (ref "C78") (pin "2") (pinfunction "2_2") (pintype "passive"))
      (node (ref "C79") (pin "2") (pinfunction "2_2") (pintype "passive"))
      (node (ref "C8") (pin "2") (pinfunction "2_2") (pintype "passive"))
      (node (ref "C80") (pin "2") (pinfunction "2_2") (pintype "passive"))
      (node (ref "C81") (pin "2") (pinfunction "2_2") (pintype "passive"))
      (node (ref "C82") (pin "2") (pinfunction "2_2") (pintype "passive"))
      (node (ref "C83") (pin "2") (pinfunction "2_2") (pintype "passive"))
      (node (ref "C84") (pin "2") (pinfunction "2_2") (pintype "passive"))
      (node (ref "C85") (pin "2") (pinfunction "2_2") (pintype "passive"))
      (node (ref "C86") (pin "2") (pinfunction "2_2") (pintype "passive"))
      (node (ref "C87") (pin "2") (pinfunction "2_2") (pintype "passive"))
      (node (ref "C88") (pin "2") (pinfunction "2_2") (pintype "passive"))
      (node (ref "C89") (pin "2") (pinfunction "2_2") (pintype "passive"))
      (node (ref "C9") (pin "2") (pinfunction "2_2") (pintype "passive"))
      (node (ref "C90") (pin "2") (pinfunction "2_2") (pintype "passive"))
      (node (ref "C91") (pin "1") (pinfunction "1_1") (pintype "passive"))
      (node (ref "C92") (pin "2") (pinfunction "2_2") (pintype "passive"))
      (node (ref "C93") (pin "2") (pinfunction "2_2") (pintype "passive"))
      (node (ref "GND") (pin "TP") (pinfunction "TP_TP") (pintype "input"))
      (node (ref "GND75") (pin "TP") (pinfunction "TP_TP") (pintype "input"))
      (node (ref "GND77") (pin "TP") (pinfunction "TP_TP") (pintype "input"))
      (node (ref "R12") (pin "2") (pinfunction "2_2") (pintype "passive"))
      (node (ref "R15") (pin "2") (pinfunction "2_2") (pintype "passive"))
      (node (ref "R18") (pin "2") (pinfunction "2_2") (pintype "passive"))
      (node (ref "R22") (pin "1") (pinfunction "1_1") (pintype "passive"))
      (node (ref "R2X") (pin "2") (pinfunction "2_2") (pintype "passive"))
      (node (ref "R3") (pin "2") (pinfunction "2_2") (pintype "passive"))
      (node (ref "R6") (pin "2") (pinfunction "2_2") (pintype "passive"))
      (node (ref "R9") (pin "2") (pinfunction "2_2") (pintype "passive"))
      (node (ref "SENSOR") (pin "A21") (pinfunction "GND_A21") (pintype "power_in"))
      (node (ref "SENSOR") (pin "A25") (pinfunction "GND_A25") (pintype "power_in"))
      (node (ref "SENSOR") (pin "A28") (pinfunction "GND_A28") (pintype "power_in"))
      (node (ref "SENSOR") (pin "A29") (pinfunction "GND_A29") (pintype "power_in"))
      (node (ref "SENSOR") (pin "A9") (pinfunction "GND_A9") (pintype "power_in"))
      (node (ref "SENSOR") (pin "B22") (pinfunction "GND_B22") (pintype "power_in"))
      (node (ref "SENSOR") (pin "B26") (pinfunction "GND_B26") (pintype "power_in"))
      (node (ref "SENSOR") (pin "B27") (pinfunction "GND_B27") (pintype "power_in"))
      (node (ref "SENSOR") (pin "B28") (pinfunction "GND_B28") (pintype "power_in"))
      (node (ref "SENSOR") (pin "B5") (pinfunction "GND_B5") (pintype "power_in"))
      (node (ref "SENSOR") (pin "C15") (pinfunction "GND_C15") (pintype "power_in"))
      (node (ref "SENSOR") (pin "C16") (pinfunction "GND_C16") (pintype "power_in"))
      (node (ref "SENSOR") (pin "C28") (pinfunction "GND_C28") (pintype "power_in"))
      (node (ref "SENSOR") (pin "D2") (pinfunction "GND_D2") (pintype "power_in"))
      (node (ref "SENSOR") (pin "D25") (pinfunction "GND_D25") (pintype "power_in"))
      (node (ref "SENSOR") (pin "D27") (pinfunction "GND_D27") (pintype "power_in"))
      (node (ref "SENSOR") (pin "D29") (pinfunction "GND_D29") (pintype "power_in"))
      (node (ref "SENSOR") (pin "E15") (pinfunction "GND_E15") (pintype "power_in"))
      (node (ref "SENSOR") (pin "E16") (pinfunction "GND_E16") (pintype "power_in"))
      (node (ref "SENSOR") (pin "E25") (pinfunction "GND_E25") (pintype "power_in"))
      (node (ref "SENSOR") (pin "E27") (pinfunction "GND_E27") (pintype "power_in"))
      (node (ref "SENSOR") (pin "E3") (pinfunction "GND_E3") (pintype "power_in"))
      (node (ref "SENSOR") (pin "F27") (pinfunction "GND_F27") (pintype "power_in"))
      (node (ref "SENSOR") (pin "G5") (pinfunction "GND_G5") (pintype "power_in"))
      (node (ref "SENSOR") (pin "H1") (pinfunction "GND_H1") (pintype "power_in"))
      (node (ref "SENSOR") (pin "H21") (pinfunction "GND_H21") (pintype "power_in"))
      (node (ref "SENSOR") (pin "H25") (pinfunction "GND_H25") (pintype "power_in"))
      (node (ref "SENSOR") (pin "H27") (pinfunction "GND_H27") (pintype "power_in"))
      (node (ref "SENSOR") (pin "H6") (pinfunction "GND_H6") (pintype "power_in"))
      (node (ref "SENSOR") (pin "H9") (pinfunction "GND_H9") (pintype "power_in"))
      (node (ref "U1") (pin "6") (pinfunction "ANODE_6") (pintype "input"))
      (node (ref "U2") (pin "6") (pinfunction "ANODE_6") (pintype "input"))
      (node (ref "U3") (pin "2") (pinfunction "GND_2") (pintype "power_in"))
      (node (ref "U3") (pin "EP") (pinfunction "EP_EP") (pintype "power_in"))
      (node (ref "U4") (pin "5") (pinfunction "DIR3_5") (pintype "input"))
      (node (ref "U4") (pin "7") (pinfunction "~{OE}_7") (pintype "input"))
      (node (ref "U4") (pin "8") (pinfunction "GND_8") (pintype "passive"))
      (node (ref "U5") (pin "6") (pinfunction "DIR4_6") (pintype "input"))
      (node (ref "U5") (pin "7") (pinfunction "~{OE}_7") (pintype "input"))
      (node (ref "U5") (pin "8") (pinfunction "GND_8") (pintype "passive"))
      (node (ref "U6") (pin "16") (pinfunction "DIR2_16") (pintype "input"))
      (node (ref "U6") (pin "7") (pinfunction "~{OE}_7") (pintype "input"))
      (node (ref "U6") (pin "8") (pinfunction "GND_8") (pintype "passive"))
      (node (ref "U7") (pin "4") (pinfunction "GND_4") (pintype "power_in"))
      (node (ref "U7") (pin "5") (pinfunction "A2_5") (pintype "input"))
      (node (ref "U7") (pin "6") (pinfunction "A1_6") (pintype "input"))
      (node (ref "U7") (pin "7") (pinfunction "A0_7") (pintype "input"))
      (node (ref "UEP") (pin "1") (pinfunction "A0_1") (pintype "input"))
      (node (ref "UEP") (pin "2") (pinfunction "A1_2") (pintype "input"))
      (node (ref "UEP") (pin "3") (pinfunction "A2_3") (pintype "input"))
      (node (ref "UEP") (pin "4") (pinfunction "GND_4") (pintype "passive"))
      (node (ref "UEP") (pin "EP") (pinfunction "EP_EP") (pintype "passive"))
      (node (ref "UNE") (pin "4") (pinfunction "VSS_4") (pintype "power_in"))
      (node (ref "UNE") (pin "EP") (pinfunction "EP_EP") (pintype "passive"))
      (node (ref "UNN") (pin "4") (pinfunction "VSS_4") (pintype "power_in"))
      (node (ref "UNN") (pin "EP") (pinfunction "EP_EP") (pintype "passive"))
      (node (ref "UNW") (pin "4") (pinfunction "VSS_4") (pintype "power_in"))
      (node (ref "UNW") (pin "EP") (pinfunction "EP_EP") (pintype "passive"))
      (node (ref "USE") (pin "4") (pinfunction "VSS_4") (pintype "power_in"))
      (node (ref "USE") (pin "EP") (pinfunction "EP_EP") (pintype "passive"))
      (node (ref "USS") (pin "4") (pinfunction "VSS_4") (pintype "power_in"))
      (node (ref "USS") (pin "EP") (pinfunction "EP_EP") (pintype "passive"))
      (node (ref "USW") (pin "4") (pinfunction "VSS_4") (pintype "power_in"))
      (node (ref "USW") (pin "EP") (pinfunction "EP_EP") (pintype "passive"))
      (node (ref "X-NORTH") (pin "102") (pinfunction "102_102") (pintype "bidirectional"))
      (node (ref "X-NORTH") (pin "103") (pinfunction "103_103") (pintype "bidirectional"))
      (node (ref "X-NORTH") (pin "108") (pinfunction "108_108") (pintype "bidirectional"))
      (node (ref "X-NORTH") (pin "114") (pinfunction "114_114") (pintype "bidirectional"))
      (node (ref "X-NORTH") (pin "12") (pinfunction "12_12") (pintype "bidirectional"))
      (node (ref "X-NORTH") (pin "120") (pinfunction "120_120") (pintype "bidirectional"))
      (node (ref "X-NORTH") (pin "126") (pinfunction "126_126") (pintype "bidirectional"))
      (node (ref "X-NORTH") (pin "132") (pinfunction "132_132") (pintype "bidirectional"))
      (node (ref "X-NORTH") (pin "138") (pinfunction "138_138") (pintype "bidirectional"))
      (node (ref "X-NORTH") (pin "139") (pinfunction "139_139") (pintype "bidirectional"))
      (node (ref "X-NORTH") (pin "18") (pinfunction "18_18") (pintype "bidirectional"))
      (node (ref "X-NORTH") (pin "24") (pinfunction "24_24") (pintype "bidirectional"))
      (node (ref "X-NORTH") (pin "30") (pinfunction "30_30") (pintype "bidirectional"))
      (node (ref "X-NORTH") (pin "36") (pinfunction "36_36") (pintype "bidirectional"))
      (node (ref "X-NORTH") (pin "42") (pinfunction "42_42") (pintype "bidirectional"))
      (node (ref "X-NORTH") (pin "43") (pinfunction "43_43") (pintype "bidirectional"))
      (node (ref "X-NORTH") (pin "48") (pinfunction "48_48") (pintype "bidirectional"))
      (node (ref "X-NORTH") (pin "54") (pinfunction "54_54") (pintype "bidirectional"))
      (node (ref "X-NORTH") (pin "60") (pinfunction "60_60") (pintype "bidirectional"))
      (node (ref "X-NORTH") (pin "66") (pinfunction "66_66") (pintype "bidirectional"))
      (node (ref "X-NORTH") (pin "72") (pinfunction "72_72") (pintype "bidirectional"))
      (node (ref "X-NORTH") (pin "78") (pinfunction "78_78") (pintype "bidirectional"))
      (node (ref "X-NORTH") (pin "84") (pinfunction "84_84") (pintype "bidirectional"))
      (node (ref "X-NORTH") (pin "90") (pinfunction "90_90") (pintype "bidirectional"))
      (node (ref "X-NORTH") (pin "96") (pinfunction "96_96") (pintype "bidirectional"))
      (node (ref "X-SOUTH") (pin "102") (pinfunction "102_102") (pintype "bidirectional"))
      (node (ref "X-SOUTH") (pin "103") (pinfunction "103_103") (pintype "bidirectional"))
      (node (ref "X-SOUTH") (pin "108") (pinfunction "108_108") (pintype "bidirectional"))
      (node (ref "X-SOUTH") (pin "114") (pinfunction "114_114") (pintype "bidirectional"))
      (node (ref "X-SOUTH") (pin "12") (pinfunction "12_12") (pintype "bidirectional"))
      (node (ref "X-SOUTH") (pin "120") (pinfunction "120_120") (pintype "bidirectional"))
      (node (ref "X-SOUTH") (pin "126") (pinfunction "126_126") (pintype "bidirectional"))
      (node (ref "X-SOUTH") (pin "132") (pinfunction "132_132") (pintype "bidirectional"))
      (node (ref "X-SOUTH") (pin "138") (pinfunction "138_138") (pintype "bidirectional"))
      (node (ref "X-SOUTH") (pin "139") (pinfunction "139_139") (pintype "bidirectional"))
      (node (ref "X-SOUTH") (pin "18") (pinfunction "18_18") (pintype "bidirectional"))
      (node (ref "X-SOUTH") (pin "24") (pinfunction "24_24") (pintype "bidirectional"))
      (node (ref "X-SOUTH") (pin "30") (pinfunction "30_30") (pintype "bidirectional"))
      (node (ref "X-SOUTH") (pin "36") (pinfunction "36_36") (pintype "bidirectional"))
      (node (ref "X-SOUTH") (pin "42") (pinfunction "42_42") (pintype "bidirectional"))
      (node (ref "X-SOUTH") (pin "43") (pinfunction "43_43") (pintype "bidirectional"))
      (node (ref "X-SOUTH") (pin "48") (pinfunction "48_48") (pintype "bidirectional"))
      (node (ref "X-SOUTH") (pin "54") (pinfunction "54_54") (pintype "bidirectional"))
      (node (ref "X-SOUTH") (pin "60") (pinfunction "60_60") (pintype "bidirectional"))
      (node (ref "X-SOUTH") (pin "66") (pinfunction "66_66") (pintype "bidirectional"))
      (node (ref "X-SOUTH") (pin "72") (pinfunction "72_72") (pintype "bidirectional"))
      (node (ref "X-SOUTH") (pin "78") (pinfunction "78_78") (pintype "bidirectional"))
      (node (ref "X-SOUTH") (pin "84") (pinfunction "84_84") (pintype "bidirectional"))
      (node (ref "X-SOUTH") (pin "90") (pinfunction "90_90") (pintype "bidirectional"))
      (node (ref "X-SOUTH") (pin "96") (pinfunction "96_96") (pintype "bidirectional"))
    )
    (net (code "4") (name "N$38") (class "Default")
      (node (ref "SENSOR") (pin "F4") (pinfunction "DIO1_F4") (pintype "output"))
    )
    (net (code "5") (name "N$39") (class "Default")
      (node (ref "SENSOR") (pin "E4") (pinfunction "DIO2_E4") (pintype "output"))
    )
    (net (code "6") (name "N$40") (class "Default")
      (node (ref "SENSOR") (pin "H4") (pinfunction "DIO3_H4") (pintype "output"))
    )
    (net (code "7") (name "N$41") (class "Default")
      (node (ref "SENSOR") (pin "G3") (pinfunction "DIO4_G3") (pintype "output"))
    )
    (net (code "8") (name "N$42") (class "Default")
      (node (ref "SENSOR") (pin "A2") (pinfunction "TANA_A2") (pintype "output"))
    )
    (net (code "9") (name "N00_N") (class "Default")
      (node (ref "R25") (pin "2") (pinfunction "2_2") (pintype "passive"))
      (node (ref "SENSOR") (pin "E6") (pinfunction "LVDS_CLK_P_E6") (pintype "input"))
      (node (ref "X-NORTH") (pin "16") (pinfunction "16_16") (pintype "bidirectional"))
    )
    (net (code "10") (name "N00_P") (class "Default")
      (node (ref "R25") (pin "1") (pinfunction "1_1") (pintype "passive"))
      (node (ref "SENSOR") (pin "E5") (pinfunction "LVDS_CLK_N_E5") (pintype "input"))
      (node (ref "X-NORTH") (pin "14") (pinfunction "14_14") (pintype "bidirectional"))
    )
    (net (code "11") (name "N01_N") (class "Default")
      (node (ref "SENSOR") (pin "G7") (pinfunction "OUTCLK_P_G7") (pintype "output"))
      (node (ref "X-NORTH") (pin "17") (pinfunction "17_17") (pintype "bidirectional"))
    )
    (net (code "12") (name "N01_P") (class "Default")
      (node (ref "SENSOR") (pin "G6") (pinfunction "OUTCLK_N_G6") (pintype "output"))
      (node (ref "X-NORTH") (pin "15") (pinfunction "15_15") (pintype "bidirectional"))
    )
    (net (code "13") (name "N02_N") (class "Default")
      (node (ref "SENSOR") (pin "F7") (pinfunction "OUT33_P_F7") (pintype "output"))
      (node (ref "X-NORTH") (pin "22") (pinfunction "22_22") (pintype "bidirectional"))
    )
    (net (code "14") (name "N02_P") (class "Default")
      (node (ref "SENSOR") (pin "F6") (pinfunction "OUT33_N_F6") (pintype "output"))
      (node (ref "X-NORTH") (pin "20") (pinfunction "20_20") (pintype "bidirectional"))
    )
    (net (code "15") (name "N03_N") (class "Default")
      (node (ref "X-NORTH") (pin "23") (pinfunction "23_23") (pintype "bidirectional"))
    )
    (net (code "16") (name "N03_P") (class "Default")
      (node (ref "X-NORTH") (pin "21") (pinfunction "21_21") (pintype "bidirectional"))
    )
    (net (code "17") (name "N04_N") (class "Default")
      (node (ref "SENSOR") (pin "E8") (pinfunction "OUT35_P_E8") (pintype "output"))
      (node (ref "X-NORTH") (pin "28") (pinfunction "28_28") (pintype "bidirectional"))
    )
    (net (code "18") (name "N04_P") (class "Default")
      (node (ref "SENSOR") (pin "E7") (pinfunction "OUT35_N_E7") (pintype "output"))
      (node (ref "X-NORTH") (pin "26") (pinfunction "26_26") (pintype "bidirectional"))
    )
    (net (code "19") (name "N05_N") (class "Default")
      (node (ref "SENSOR") (pin "H8") (pinfunction "OUT34_P_H8") (pintype "output"))
      (node (ref "X-NORTH") (pin "29") (pinfunction "29_29") (pintype "bidirectional"))
    )
    (net (code "20") (name "N05_P") (class "Default")
      (node (ref "SENSOR") (pin "H7") (pinfunction "OUT34_N_H7") (pintype "output"))
      (node (ref "X-NORTH") (pin "27") (pinfunction "27_27") (pintype "bidirectional"))
    )
    (net (code "21") (name "N06_N") (class "Default")
      (node (ref "SENSOR") (pin "F9") (pinfunction "OUT37_P_F9") (pintype "output"))
      (node (ref "X-NORTH") (pin "34") (pinfunction "34_34") (pintype "bidirectional"))
    )
    (net (code "22") (name "N06_P") (class "Default")
      (node (ref "SENSOR") (pin "F8") (pinfunction "OUT37_N_F8") (pintype "output"))
      (node (ref "X-NORTH") (pin "32") (pinfunction "32_32") (pintype "bidirectional"))
    )
    (net (code "23") (name "N07_N") (class "Default")
      (node (ref "SENSOR") (pin "G9") (pinfunction "OUT36_P_G9") (pintype "output"))
      (node (ref "X-NORTH") (pin "35") (pinfunction "35_35") (pintype "bidirectional"))
    )
    (net (code "24") (name "N07_P") (class "Default")
      (node (ref "SENSOR") (pin "G8") (pinfunction "OUT36_N_G8") (pintype "output"))
      (node (ref "X-NORTH") (pin "33") (pinfunction "33_33") (pintype "bidirectional"))
    )
    (net (code "25") (name "N08_N") (class "Default")
      (node (ref "SENSOR") (pin "E10") (pinfunction "OUT38_P_E10") (pintype "output"))
      (node (ref "X-NORTH") (pin "40") (pinfunction "40_40") (pintype "bidirectional"))
    )
    (net (code "26") (name "N08_P") (class "Default")
      (node (ref "SENSOR") (pin "E9") (pinfunction "OUT38_N_E9") (pintype "output"))
      (node (ref "X-NORTH") (pin "38") (pinfunction "38_38") (pintype "bidirectional"))
    )
    (net (code "27") (name "N09_N") (class "Default")
      (node (ref "SENSOR") (pin "G11") (pinfunction "OUT39_P_G11") (pintype "output"))
      (node (ref "X-NORTH") (pin "41") (pinfunction "41_41") (pintype "bidirectional"))
    )
    (net (code "28") (name "N09_P") (class "Default")
      (node (ref "SENSOR") (pin "G10") (pinfunction "OUT39_N_G10") (pintype "output"))
      (node (ref "X-NORTH") (pin "39") (pinfunction "39_39") (pintype "bidirectional"))
    )
    (net (code "29") (name "N10_N") (class "Default")
      (node (ref "SENSOR") (pin "F11") (pinfunction "OUT40_P_F11") (pintype "output"))
      (node (ref "X-NORTH") (pin "46") (pinfunction "46_46") (pintype "bidirectional"))
    )
    (net (code "30") (name "N10_P") (class "Default")
      (node (ref "SENSOR") (pin "F10") (pinfunction "OUT40_N_F10") (pintype "output"))
      (node (ref "X-NORTH") (pin "44") (pinfunction "44_44") (pintype "bidirectional"))
    )
    (net (code "31") (name "N11_N") (class "Default")
      (node (ref "SENSOR") (pin "H12") (pinfunction "OUT41_P_H12") (pintype "output"))
      (node (ref "X-NORTH") (pin "47") (pinfunction "47_47") (pintype "bidirectional"))
    )
    (net (code "32") (name "N11_P") (class "Default")
      (node (ref "SENSOR") (pin "H11") (pinfunction "OUT41_N_H11") (pintype "output"))
      (node (ref "X-NORTH") (pin "45") (pinfunction "45_45") (pintype "bidirectional"))
    )
    (net (code "33") (name "N12_N") (class "Default")
      (node (ref "SENSOR") (pin "E12") (pinfunction "OUT42_P_E12") (pintype "output"))
      (node (ref "X-NORTH") (pin "52") (pinfunction "52_52") (pintype "bidirectional"))
    )
    (net (code "34") (name "N12_P") (class "Default")
      (node (ref "SENSOR") (pin "E11") (pinfunction "OUT42_N_E11") (pintype "output"))
      (node (ref "X-NORTH") (pin "50") (pinfunction "50_50") (pintype "bidirectional"))
    )
    (net (code "35") (name "N13_N") (class "Default")
      (node (ref "SENSOR") (pin "G13") (pinfunction "OUT43_P_G13") (pintype "output"))
      (node (ref "X-NORTH") (pin "53") (pinfunction "53_53") (pintype "bidirectional"))
    )
    (net (code "36") (name "N13_P") (class "Default")
      (node (ref "SENSOR") (pin "G12") (pinfunction "OUT43_N_G12") (pintype "output"))
      (node (ref "X-NORTH") (pin "51") (pinfunction "51_51") (pintype "bidirectional"))
    )
    (net (code "37") (name "N14_N") (class "Default")
      (node (ref "SENSOR") (pin "F13") (pinfunction "OUT44_P_F13") (pintype "output"))
      (node (ref "X-NORTH") (pin "58") (pinfunction "58_58") (pintype "bidirectional"))
    )
    (net (code "38") (name "N14_P") (class "Default")
      (node (ref "SENSOR") (pin "F12") (pinfunction "OUT44_N_F12") (pintype "output"))
      (node (ref "X-NORTH") (pin "56") (pinfunction "56_56") (pintype "bidirectional"))
    )
    (net (code "39") (name "N15_N") (class "Default")
      (node (ref "SENSOR") (pin "H14") (pinfunction "OUT45_P_H14") (pintype "output"))
      (node (ref "X-NORTH") (pin "59") (pinfunction "59_59") (pintype "bidirectional"))
    )
    (net (code "40") (name "N15_P") (class "Default")
      (node (ref "SENSOR") (pin "H13") (pinfunction "OUT45_N_H13") (pintype "output"))
      (node (ref "X-NORTH") (pin "57") (pinfunction "57_57") (pintype "bidirectional"))
    )
    (net (code "41") (name "N16_N") (class "Default")
      (node (ref "SENSOR") (pin "E14") (pinfunction "OUT46_P_E14") (pintype "output"))
      (node (ref "X-NORTH") (pin "64") (pinfunction "64_64") (pintype "bidirectional"))
    )
    (net (code "42") (name "N16_P") (class "Default")
      (node (ref "SENSOR") (pin "E13") (pinfunction "OUT46_N_E13") (pintype "output"))
      (node (ref "X-NORTH") (pin "62") (pinfunction "62_62") (pintype "bidirectional"))
    )
    (net (code "43") (name "N17_N") (class "Default")
      (node (ref "SENSOR") (pin "G15") (pinfunction "OUT47_P_G15") (pintype "output"))
      (node (ref "X-NORTH") (pin "65") (pinfunction "65_65") (pintype "bidirectional"))
    )
    (net (code "44") (name "N17_P") (class "Default")
      (node (ref "SENSOR") (pin "G14") (pinfunction "OUT47_N_G14") (pintype "output"))
      (node (ref "X-NORTH") (pin "63") (pinfunction "63_63") (pintype "bidirectional"))
    )
    (net (code "45") (name "N18_N") (class "Default")
      (node (ref "SENSOR") (pin "F15") (pinfunction "OUT48_P_F15") (pintype "output"))
      (node (ref "X-NORTH") (pin "70") (pinfunction "70_70") (pintype "bidirectional"))
    )
    (net (code "46") (name "N18_P") (class "Default")
      (node (ref "SENSOR") (pin "F14") (pinfunction "OUT48_N_F14") (pintype "output"))
      (node (ref "X-NORTH") (pin "68") (pinfunction "68_68") (pintype "bidirectional"))
    )
    (net (code "47") (name "N19_N") (class "Default")
      (node (ref "SENSOR") (pin "G17") (pinfunction "OUT50_P_G17") (pintype "output"))
      (node (ref "X-NORTH") (pin "71") (pinfunction "71_71") (pintype "bidirectional"))
    )
    (net (code "48") (name "N19_P") (class "Default")
      (node (ref "SENSOR") (pin "G16") (pinfunction "OUT50_N_G16") (pintype "output"))
      (node (ref "X-NORTH") (pin "69") (pinfunction "69_69") (pintype "bidirectional"))
    )
    (net (code "49") (name "N20_N") (class "Default")
      (node (ref "SENSOR") (pin "F17") (pinfunction "OUT49_P_F17") (pintype "output"))
      (node (ref "X-NORTH") (pin "76") (pinfunction "76_76") (pintype "bidirectional"))
    )
    (net (code "50") (name "N20_P") (class "Default")
      (node (ref "SENSOR") (pin "F16") (pinfunction "OUT49_N_F16") (pintype "output"))
      (node (ref "X-NORTH") (pin "74") (pinfunction "74_74") (pintype "bidirectional"))
    )
    (net (code "51") (name "N21_N") (class "Default")
      (node (ref "SENSOR") (pin "H18") (pinfunction "OUT52_P_H18") (pintype "output"))
      (node (ref "X-NORTH") (pin "77") (pinfunction "77_77") (pintype "bidirectional"))
    )
    (net (code "52") (name "N21_P") (class "Default")
      (node (ref "SENSOR") (pin "H17") (pinfunction "OUT52_N_H17") (pintype "output"))
      (node (ref "X-NORTH") (pin "75") (pinfunction "75_75") (pintype "bidirectional"))
    )
    (net (code "53") (name "N22_N") (class "Default")
      (node (ref "SENSOR") (pin "E18") (pinfunction "OUT51_P_E18") (pintype "output"))
      (node (ref "X-NORTH") (pin "82") (pinfunction "82_82") (pintype "bidirectional"))
    )
    (net (code "54") (name "N22_P") (class "Default")
      (node (ref "SENSOR") (pin "E17") (pinfunction "OUT51_N_E17") (pintype "output"))
      (node (ref "X-NORTH") (pin "80") (pinfunction "80_80") (pintype "bidirectional"))
    )
    (net (code "55") (name "N23_N") (class "Default")
      (node (ref "SENSOR") (pin "G19") (pinfunction "OUT54_P_G19") (pintype "output"))
      (node (ref "X-NORTH") (pin "83") (pinfunction "83_83") (pintype "bidirectional"))
    )
    (net (code "56") (name "N23_P") (class "Default")
      (node (ref "SENSOR") (pin "G18") (pinfunction "OUT54_N_G18") (pintype "output"))
      (node (ref "X-NORTH") (pin "81") (pinfunction "81_81") (pintype "bidirectional"))
    )
    (net (code "57") (name "N24_N") (class "Default")
      (node (ref "SENSOR") (pin "F19") (pinfunction "OUT53_P_F19") (pintype "output"))
      (node (ref "X-NORTH") (pin "88") (pinfunction "88_88") (pintype "bidirectional"))
    )
    (net (code "58") (name "N24_P") (class "Default")
      (node (ref "SENSOR") (pin "F18") (pinfunction "OUT53_N_F18") (pintype "output"))
      (node (ref "X-NORTH") (pin "86") (pinfunction "86_86") (pintype "bidirectional"))
    )
    (net (code "59") (name "N25_N") (class "Default")
      (node (ref "SENSOR") (pin "H20") (pinfunction "OUT56_P_H20") (pintype "output"))
      (node (ref "X-NORTH") (pin "89") (pinfunction "89_89") (pintype "bidirectional"))
    )
    (net (code "60") (name "N25_P") (class "Default")
      (node (ref "SENSOR") (pin "H19") (pinfunction "OUT56_N_H19") (pintype "output"))
      (node (ref "X-NORTH") (pin "87") (pinfunction "87_87") (pintype "bidirectional"))
    )
    (net (code "61") (name "N26_N") (class "Default")
      (node (ref "SENSOR") (pin "E20") (pinfunction "OUT55_P_E20") (pintype "output"))
      (node (ref "X-NORTH") (pin "94") (pinfunction "94_94") (pintype "bidirectional"))
    )
    (net (code "62") (name "N26_P") (class "Default")
      (node (ref "SENSOR") (pin "E19") (pinfunction "OUT55_N_E19") (pintype "output"))
      (node (ref "X-NORTH") (pin "92") (pinfunction "92_92") (pintype "bidirectional"))
    )
    (net (code "63") (name "N27_N") (class "Default")
      (node (ref "SENSOR") (pin "G21") (pinfunction "OUT58_P_G21") (pintype "output"))
      (node (ref "X-NORTH") (pin "95") (pinfunction "95_95") (pintype "bidirectional"))
    )
    (net (code "64") (name "N27_P") (class "Default")
      (node (ref "SENSOR") (pin "G20") (pinfunction "OUT58_N_G20") (pintype "output"))
      (node (ref "X-NORTH") (pin "93") (pinfunction "93_93") (pintype "bidirectional"))
    )
    (net (code "65") (name "N28_N") (class "Default")
      (node (ref "SENSOR") (pin "F21") (pinfunction "OUT57_P_F21") (pintype "output"))
      (node (ref "X-NORTH") (pin "100") (pinfunction "100_100") (pintype "bidirectional"))
    )
    (net (code "66") (name "N28_P") (class "Default")
      (node (ref "SENSOR") (pin "F20") (pinfunction "OUT57_N_F20") (pintype "output"))
      (node (ref "X-NORTH") (pin "98") (pinfunction "98_98") (pintype "bidirectional"))
    )
    (net (code "67") (name "N29_N") (class "Default")
      (node (ref "SENSOR") (pin "G23") (pinfunction "OUT61_P_G23") (pintype "output"))
      (node (ref "X-NORTH") (pin "101") (pinfunction "101_101") (pintype "bidirectional"))
    )
    (net (code "68") (name "N29_P") (class "Default")
      (node (ref "SENSOR") (pin "G22") (pinfunction "OUT61_N_G22") (pintype "output"))
      (node (ref "X-NORTH") (pin "99") (pinfunction "99_99") (pintype "bidirectional"))
    )
    (net (code "69") (name "N30_N") (class "Default")
      (node (ref "SENSOR") (pin "E22") (pinfunction "OUT59_P_E22") (pintype "output"))
      (node (ref "X-NORTH") (pin "106") (pinfunction "106_106") (pintype "bidirectional"))
    )
    (net (code "70") (name "N30_P") (class "Default")
      (node (ref "SENSOR") (pin "E21") (pinfunction "OUT59_N_E21") (pintype "output"))
      (node (ref "X-NORTH") (pin "104") (pinfunction "104_104") (pintype "bidirectional"))
    )
    (net (code "71") (name "N31_N") (class "Default")
      (node (ref "SENSOR") (pin "H24") (pinfunction "OUT63_P_H24") (pintype "output"))
      (node (ref "X-NORTH") (pin "107") (pinfunction "107_107") (pintype "bidirectional"))
    )
    (net (code "72") (name "N31_P") (class "Default")
      (node (ref "SENSOR") (pin "H23") (pinfunction "OUT63_N_H23") (pintype "output"))
      (node (ref "X-NORTH") (pin "105") (pinfunction "105_105") (pintype "bidirectional"))
    )
    (net (code "73") (name "N32_N") (class "Default")
      (node (ref "SENSOR") (pin "F23") (pinfunction "OUT60_P_F23") (pintype "output"))
      (node (ref "X-NORTH") (pin "112") (pinfunction "112_112") (pintype "bidirectional"))
    )
    (net (code "74") (name "N32_P") (class "Default")
      (node (ref "SENSOR") (pin "F22") (pinfunction "OUT60_N_F22") (pintype "output"))
      (node (ref "X-NORTH") (pin "110") (pinfunction "110_110") (pintype "bidirectional"))
    )
    (net (code "75") (name "N33_N") (class "Default")
      (node (ref "SENSOR") (pin "G25") (pinfunction "OUT64_P_G25") (pintype "output"))
      (node (ref "X-NORTH") (pin "113") (pinfunction "113_113") (pintype "bidirectional"))
    )
    (net (code "76") (name "N33_P") (class "Default")
      (node (ref "SENSOR") (pin "G24") (pinfunction "OUT64_N_G24") (pintype "output"))
      (node (ref "X-NORTH") (pin "111") (pinfunction "111_111") (pintype "bidirectional"))
    )
    (net (code "77") (name "N34_N") (class "Default")
      (node (ref "SENSOR") (pin "E24") (pinfunction "OUT62_P_E24") (pintype "output"))
      (node (ref "X-NORTH") (pin "118") (pinfunction "118_118") (pintype "bidirectional"))
    )
    (net (code "78") (name "N34_P") (class "Default")
      (node (ref "SENSOR") (pin "E23") (pinfunction "OUT62_N_E23") (pintype "output"))
      (node (ref "X-NORTH") (pin "116") (pinfunction "116_116") (pintype "bidirectional"))
    )
    (net (code "79") (name "N35_N") (class "Default")
      (node (ref "U6") (pin "4") (pinfunction "A4_4") (pintype "bidirectional"))
      (node (ref "X-NORTH") (pin "119") (pinfunction "119_119") (pintype "bidirectional"))
    )
    (net (code "80") (name "N35_P") (class "Default")
      (node (ref "U6") (pin "3") (pinfunction "A3_3") (pintype "bidirectional"))
      (node (ref "X-NORTH") (pin "117") (pinfunction "117_117") (pintype "bidirectional"))
    )
    (net (code "81") (name "N36_N") (class "Default")
      (node (ref "X-NORTH") (pin "124") (pinfunction "124_124") (pintype "bidirectional"))
    )
    (net (code "82") (name "N36_P") (class "Default")
      (node (ref "X-NORTH") (pin "122") (pinfunction "122_122") (pintype "bidirectional"))
    )
    (net (code "83") (name "N37_N") (class "Default")
      (node (ref "U5") (pin "3") (pinfunction "A3_3") (pintype "bidirectional"))
      (node (ref "X-NORTH") (pin "125") (pinfunction "125_125") (pintype "bidirectional"))
    )
    (net (code "84") (name "N37_P") (class "Default")
      (node (ref "U5") (pin "4") (pinfunction "A4_4") (pintype "bidirectional"))
      (node (ref "X-NORTH") (pin "123") (pinfunction "123_123") (pintype "bidirectional"))
    )
    (net (code "85") (name "N38_N") (class "Default")
      (node (ref "U6") (pin "2") (pinfunction "A2_2") (pintype "bidirectional"))
      (node (ref "X-NORTH") (pin "130") (pinfunction "130_130") (pintype "bidirectional"))
    )
    (net (code "86") (name "N38_P") (class "Default")
      (node (ref "U6") (pin "1") (pinfunction "A1_1") (pintype "bidirectional"))
      (node (ref "X-NORTH") (pin "128") (pinfunction "128_128") (pintype "bidirectional"))
    )
    (net (code "87") (name "N39_N") (class "Default")
      (node (ref "U5") (pin "1") (pinfunction "A1_1") (pintype "bidirectional"))
      (node (ref "X-NORTH") (pin "131") (pinfunction "131_131") (pintype "bidirectional"))
    )
    (net (code "88") (name "N39_P") (class "Default")
      (node (ref "U5") (pin "2") (pinfunction "A2_2") (pintype "bidirectional"))
      (node (ref "X-NORTH") (pin "129") (pinfunction "129_129") (pintype "bidirectional"))
    )
    (net (code "89") (name "N_CHK_EN") (class "Default")
      (node (ref "X-NORTH") (pin "8") (pinfunction "8_8") (pintype "bidirectional"))
    )
    (net (code "90") (name "N_CHK_V") (class "Default")
      (node (ref "C2") (pin "1") (pinfunction "1_1") (pintype "passive"))
      (node (ref "C3") (pin "1") (pinfunction "1_1") (pintype "passive"))
      (node (ref "C4") (pin "1") (pinfunction "1_1") (pintype "passive"))
      (node (ref "R19") (pin "1") (pinfunction "1_1") (pintype "passive"))
      (node (ref "TP1") (pin "TP") (pinfunction "TP_TP") (pintype "input"))
      (node (ref "UNE") (pin "8") (pinfunction "VDD_8") (pintype "power_in"))
      (node (ref "UNN") (pin "8") (pinfunction "VDD_8") (pintype "power_in"))
      (node (ref "UNW") (pin "8") (pinfunction "VDD_8") (pintype "power_in"))
      (node (ref "X-NORTH") (pin "10") (pinfunction "10_10") (pintype "bidirectional"))
    )
    (net (code "91") (name "N_I2C_EN") (class "Default")
      (node (ref "X-NORTH") (pin "137") (pinfunction "137_137") (pintype "bidirectional"))
    )
    (net (code "92") (name "N_I2C_V") (class "Default")
      (node (ref "C1") (pin "1") (pinfunction "1_1") (pintype "passive"))
      (node (ref "R1X") (pin "1") (pinfunction "1_1") (pintype "passive"))
      (node (ref "UEP") (pin "8") (pinfunction "VCC_8") (pintype "power_in"))
      (node (ref "X-NORTH") (pin "135") (pinfunction "135_135") (pintype "bidirectional"))
    )
    (net (code "93") (name "N_REF") (class "Default")
      (node (ref "R19") (pin "2") (pinfunction "2_2") (pintype "passive"))
      (node (ref "TP2") (pin "TP") (pinfunction "TP_TP") (pintype "input"))
      (node (ref "U1") (pin "1") (pinfunction "CATHODE_1") (pintype "output"))
      (node (ref "U1") (pin "3") (pinfunction "REF_3") (pintype "input"))
      (node (ref "UNE") (pin "2") (pinfunction "VINA-_2") (pintype "input"))
      (node (ref "UNE") (pin "5") (pinfunction "VINB+_5") (pintype "input"))
      (node (ref "UNN") (pin "2") (pinfunction "VINA-_2") (pintype "input"))
      (node (ref "UNN") (pin "5") (pinfunction "VINB+_5") (pintype "input"))
      (node (ref "UNW") (pin "2") (pinfunction "VINA-_2") (pintype "input"))
      (node (ref "UNW") (pin "5") (pinfunction "VINB+_5") (pintype "input"))
    )
    (net (code "94") (name "N_SCK") (class "Default")
      (node (ref "U4") (pin "2") (pinfunction "A2_2") (pintype "bidirectional"))
      (node (ref "X-NORTH") (pin "144") (pinfunction "144_144") (pintype "bidirectional"))
    )
    (net (code "95") (name "N_SCL") (class "Default")
      (node (ref "UEP") (pin "6") (pinfunction "SCL_6") (pintype "input"))
      (node (ref "X-NORTH") (pin "143") (pinfunction "143_143") (pintype "bidirectional"))
    )
    (net (code "96") (name "N_SDA") (class "Default")
      (node (ref "UEP") (pin "5") (pinfunction "SDA_5") (pintype "bidirectional"))
      (node (ref "X-NORTH") (pin "141") (pinfunction "141_141") (pintype "bidirectional"))
    )
    (net (code "97") (name "N_SDI") (class "Default")
      (node (ref "U4") (pin "3") (pinfunction "A3_3") (pintype "bidirectional"))
      (node (ref "X-NORTH") (pin "140") (pinfunction "140_140") (pintype "bidirectional"))
    )
    (net (code "98") (name "N_SDO") (class "Default")
      (node (ref "U4") (pin "1") (pinfunction "A1_1") (pintype "bidirectional"))
      (node (ref "X-NORTH") (pin "142") (pinfunction "142_142") (pintype "bidirectional"))
    )
    (net (code "99") (name "N_SPI_EN") (class "Default")
      (node (ref "U4") (pin "4") (pinfunction "A4_4") (pintype "bidirectional"))
      (node (ref "X-NORTH") (pin "136") (pinfunction "136_136") (pintype "bidirectional"))
    )
    (net (code "100") (name "N_SPI_V") (class "Default")
      (node (ref "C59") (pin "1") (pinfunction "1_1") (pintype "passive"))
      (node (ref "U4") (pin "14") (pinfunction "VCCA_14") (pintype "power_in"))
      (node (ref "U4") (pin "15") (pinfunction "DIR1_15") (pintype "input"))
      (node (ref "U4") (pin "16") (pinfunction "DIR2_16") (pintype "input"))
      (node (ref "U4") (pin "6") (pinfunction "DIR4_6") (pintype "input"))
      (node (ref "X-NORTH") (pin "134") (pinfunction "134_134") (pintype "bidirectional"))
    )
    (net (code "101") (name "N_VE") (class "Default")
      (node (ref "C50") (pin "1") (pinfunction "1_1") (pintype "passive"))
      (node (ref "C51") (pin "1") (pinfunction "1_1") (pintype "passive"))
      (node (ref "C52") (pin "1") (pinfunction "1_1") (pintype "passive"))
      (node (ref "C53") (pin "1") (pinfunction "1_1") (pintype "passive"))
      (node (ref "C54") (pin "1") (pinfunction "1_1") (pintype "passive"))
      (node (ref "C55") (pin "1") (pinfunction "1_1") (pintype "passive"))
      (node (ref "C56") (pin "1") (pinfunction "1_1") (pintype "passive"))
      (node (ref "C67") (pin "1") (pinfunction "1_1") (pintype "passive"))
      (node (ref "C69") (pin "1") (pinfunction "1_1") (pintype "passive"))
      (node (ref "C75") (pin "1") (pinfunction "1_1") (pintype "passive"))
      (node (ref "C76") (pin "1") (pinfunction "1_1") (pintype "passive"))
      (node (ref "C77") (pin "1") (pinfunction "1_1") (pintype "passive"))
      (node (ref "C84") (pin "1") (pinfunction "1_1") (pintype "passive"))
      (node (ref "C85") (pin "1") (pinfunction "1_1") (pintype "passive"))
      (node (ref "C86") (pin "1") (pinfunction "1_1") (pintype "passive"))
      (node (ref "C93") (pin "1") (pinfunction "1_1") (pintype "passive"))
      (node (ref "SENSOR") (pin "C26") (pinfunction "VDD33_C26") (pintype "power_in"))
      (node (ref "SENSOR") (pin "C27") (pinfunction "VDD33_C27") (pintype "power_in"))
      (node (ref "SENSOR") (pin "D26") (pinfunction "VDD33_D26") (pintype "power_in"))
      (node (ref "SENSOR") (pin "D3") (pinfunction "VDD33_D3") (pintype "power_in"))
      (node (ref "SENSOR") (pin "E26") (pinfunction "VDD33_E26") (pintype "power_in"))
      (node (ref "SENSOR") (pin "F26") (pinfunction "VDD33_F26") (pintype "power_in"))
      (node (ref "SENSOR") (pin "F5") (pinfunction "VDD33_F5") (pintype "power_in"))
      (node (ref "TP7") (pin "TP") (pinfunction "TP_TP") (pintype "input"))
      (node (ref "U4") (pin "13") (pinfunction "VCCB_13") (pintype "power_in"))
      (node (ref "U5") (pin "13") (pinfunction "VCCB_13") (pintype "power_in"))
      (node (ref "U6") (pin "13") (pinfunction "VCCB_13") (pintype "power_in"))
      (node (ref "X-NORTH") (pin "109") (pinfunction "109_109") (pintype "bidirectional"))
      (node (ref "X-NORTH") (pin "115") (pinfunction "115_115") (pintype "bidirectional"))
      (node (ref "X-NORTH") (pin "121") (pinfunction "121_121") (pintype "bidirectional"))
      (node (ref "X-NORTH") (pin "127") (pinfunction "127_127") (pintype "bidirectional"))
      (node (ref "X-NORTH") (pin "133") (pinfunction "133_133") (pintype "bidirectional"))
    )
    (net (code "102") (name "N_VE_CV") (class "Default")
      (node (ref "C10") (pin "1") (pinfunction "1_1") (pintype "passive"))
      (node (ref "R7") (pin "1") (pinfunction "1_1") (pintype "passive"))
      (node (ref "X-NORTH") (pin "6") (pinfunction "6_6") (pintype "bidirectional"))
    )
    (net (code "103") (name "N_VE_OV") (class "Default")
      (node (ref "UNE") (pin "7") (pinfunction "OUTB_7") (pintype "output"))
      (node (ref "X-NORTH") (pin "5") (pinfunction "5_5") (pintype "bidirectional"))
    )
    (net (code "104") (name "N_VE_UV") (class "Default")
      (node (ref "UNE") (pin "1") (pinfunction "OUTA_1") (pintype "output"))
      (node (ref "X-NORTH") (pin "11") (pinfunction "11_11") (pintype "bidirectional"))
    )
    (net (code "105") (name "N_VN") (class "Default")
      (node (ref "C31") (pin "1") (pinfunction "1_1") (pintype "passive"))
      (node (ref "C32") (pin "1") (pinfunction "1_1") (pintype "passive"))
      (node (ref "C33") (pin "1") (pinfunction "1_1") (pintype "passive"))
      (node (ref "C34") (pin "1") (pinfunction "1_1") (pintype "passive"))
      (node (ref "C35") (pin "1") (pinfunction "1_1") (pintype "passive"))
      (node (ref "C36") (pin "1") (pinfunction "1_1") (pintype "passive"))
      (node (ref "C37") (pin "1") (pinfunction "1_1") (pintype "passive"))
      (node (ref "C38") (pin "1") (pinfunction "1_1") (pintype "passive"))
      (node (ref "C39") (pin "1") (pinfunction "1_1") (pintype "passive"))
      (node (ref "C40") (pin "1") (pinfunction "1_1") (pintype "passive"))
      (node (ref "C41") (pin "1") (pinfunction "1_1") (pintype "passive"))
      (node (ref "C42") (pin "1") (pinfunction "1_1") (pintype "passive"))
      (node (ref "C43") (pin "1") (pinfunction "1_1") (pintype "passive"))
      (node (ref "C44") (pin "1") (pinfunction "1_1") (pintype "passive"))
      (node (ref "C68") (pin "1") (pinfunction "1_1") (pintype "passive"))
      (node (ref "C70") (pin "1") (pinfunction "1_1") (pintype "passive"))
      (node (ref "C78") (pin "1") (pinfunction "1_1") (pintype "passive"))
      (node (ref "C79") (pin "1") (pinfunction "1_1") (pintype "passive"))
      (node (ref "C80") (pin "1") (pinfunction "1_1") (pintype "passive"))
      (node (ref "C87") (pin "1") (pinfunction "1_1") (pintype "passive"))
      (node (ref "C88") (pin "1") (pinfunction "1_1") (pintype "passive"))
      (node (ref "C89") (pin "1") (pinfunction "1_1") (pintype "passive"))
      (node (ref "SENSOR") (pin "A10") (pinfunction "VDD18_A10") (pintype "power_in"))
      (node (ref "SENSOR") (pin "A15") (pinfunction "VDD18_A15") (pintype "power_in"))
      (node (ref "SENSOR") (pin "A16") (pinfunction "VDD18_A16") (pintype "power_in"))
      (node (ref "SENSOR") (pin "A22") (pinfunction "VDD18_A22") (pintype "power_in"))
      (node (ref "SENSOR") (pin "A26") (pinfunction "VDD18_A26") (pintype "power_in"))
      (node (ref "SENSOR") (pin "A27") (pinfunction "VDD18_A27") (pintype "power_in"))
      (node (ref "SENSOR") (pin "B4") (pinfunction "VDD18_B4") (pintype "power_in"))
      (node (ref "SENSOR") (pin "E1") (pinfunction "VDD18_PLL_E1") (pintype "power_in"))
      (node (ref "SENSOR") (pin "H10") (pinfunction "VDD18_H10") (pintype "power_in"))
      (node (ref "SENSOR") (pin "H15") (pinfunction "VDD18_H15") (pintype "power_in"))
      (node (ref "SENSOR") (pin "H16") (pinfunction "VDD18_H16") (pintype "power_in"))
      (node (ref "SENSOR") (pin "H22") (pinfunction "VDD18_H22") (pintype "power_in"))
      (node (ref "SENSOR") (pin "H26") (pinfunction "VDD18_H26") (pintype "power_in"))
      (node (ref "SENSOR") (pin "H5") (pinfunction "VDD18_H5") (pintype "power_in"))
      (node (ref "TP5") (pin "TP") (pinfunction "TP_TP") (pintype "input"))
      (node (ref "U5") (pin "14") (pinfunction "VCCA_14") (pintype "power_in"))
      (node (ref "U5") (pin "15") (pinfunction "DIR1_15") (pintype "input"))
      (node (ref "U5") (pin "16") (pinfunction "DIR2_16") (pintype "input"))
      (node (ref "U5") (pin "5") (pinfunction "DIR3_5") (pintype "input"))
      (node (ref "U6") (pin "14") (pinfunction "VCCA_14") (pintype "power_in"))
      (node (ref "U6") (pin "15") (pinfunction "DIR1_15") (pintype "input"))
      (node (ref "U6") (pin "5") (pinfunction "DIR3_5") (pintype "input"))
      (node (ref "U6") (pin "6") (pinfunction "DIR4_6") (pintype "input"))
      (node (ref "X-NORTH") (pin "49") (pinfunction "49_49") (pintype "bidirectional"))
      (node (ref "X-NORTH") (pin "55") (pinfunction "55_55") (pintype "bidirectional"))
      (node (ref "X-NORTH") (pin "61") (pinfunction "61_61") (pintype "bidirectional"))
      (node (ref "X-NORTH") (pin "67") (pinfunction "67_67") (pintype "bidirectional"))
      (node (ref "X-NORTH") (pin "73") (pinfunction "73_73") (pintype "bidirectional"))
      (node (ref "X-NORTH") (pin "79") (pinfunction "79_79") (pintype "bidirectional"))
      (node (ref "X-NORTH") (pin "85") (pinfunction "85_85") (pintype "bidirectional"))
      (node (ref "X-NORTH") (pin "91") (pinfunction "91_91") (pintype "bidirectional"))
      (node (ref "X-NORTH") (pin "97") (pinfunction "97_97") (pintype "bidirectional"))
    )
    (net (code "106") (name "N_VN_CV") (class "Default")
      (node (ref "C9") (pin "1") (pinfunction "1_1") (pintype "passive"))
      (node (ref "R4") (pin "1") (pinfunction "1_1") (pintype "passive"))
      (node (ref "X-NORTH") (pin "4") (pinfunction "4_4") (pintype "bidirectional"))
    )
    (net (code "107") (name "N_VN_OV") (class "Default")
      (node (ref "UNN") (pin "7") (pinfunction "OUTB_7") (pintype "output"))
      (node (ref "X-NORTH") (pin "3") (pinfunction "3_3") (pintype "bidirectional"))
    )
    (net (code "108") (name "N_VN_UV") (class "Default")
      (node (ref "UNN") (pin "1") (pinfunction "OUTA_1") (pintype "output"))
      (node (ref "X-NORTH") (pin "9") (pinfunction "9_9") (pintype "bidirectional"))
    )
    (net (code "109") (name "N_VW") (class "Default")
      (node (ref "C57") (pin "1") (pinfunction "1_1") (pintype "passive"))
      (node (ref "C58") (pin "1") (pinfunction "1_1") (pintype "passive"))
      (node (ref "C92") (pin "1") (pinfunction "1_1") (pintype "passive"))
      (node (ref "SENSOR") (pin "E2") (pinfunction "VDD_RES_E2") (pintype "power_in"))
      (node (ref "SENSOR") (pin "G4") (pinfunction "VDD_RES_G4") (pintype "power_in"))
      (node (ref "TP8") (pin "TP") (pinfunction "TP_TP") (pintype "input"))
      (node (ref "X-NORTH") (pin "13") (pinfunction "13_13") (pintype "bidirectional"))
      (node (ref "X-NORTH") (pin "19") (pinfunction "19_19") (pintype "bidirectional"))
      (node (ref "X-NORTH") (pin "25") (pinfunction "25_25") (pintype "bidirectional"))
      (node (ref "X-NORTH") (pin "31") (pinfunction "31_31") (pintype "bidirectional"))
      (node (ref "X-NORTH") (pin "37") (pinfunction "37_37") (pintype "bidirectional"))
    )
    (net (code "110") (name "N_VW_CV") (class "Default")
      (node (ref "C8") (pin "1") (pinfunction "1_1") (pintype "passive"))
      (node (ref "R1") (pin "1") (pinfunction "1_1") (pintype "passive"))
      (node (ref "X-NORTH") (pin "2") (pinfunction "2_2") (pintype "bidirectional"))
    )
    (net (code "111") (name "N_VW_OV") (class "Default")
      (node (ref "UNW") (pin "7") (pinfunction "OUTB_7") (pintype "output"))
      (node (ref "X-NORTH") (pin "1") (pinfunction "1_1") (pintype "bidirectional"))
    )
    (net (code "112") (name "N_VW_UV") (class "Default")
      (node (ref "UNW") (pin "1") (pinfunction "OUTA_1") (pintype "output"))
      (node (ref "X-NORTH") (pin "7") (pinfunction "7_7") (pintype "bidirectional"))
    )
    (net (code "113") (name "Net-(SENSORB-CMDN)") (class "Default")
      (node (ref "C61") (pin "1") (pinfunction "1_1") (pintype "passive"))
      (node (ref "SENSOR") (pin "F1") (pinfunction "CMDN_F1") (pintype "bidirectional"))
    )
    (net (code "114") (name "Net-(SENSORB-CMDP)") (class "Default")
      (node (ref "C22") (pin "2") (pinfunction "2_2") (pintype "passive"))
      (node (ref "SENSOR") (pin "F2") (pinfunction "CMDP_F2") (pintype "bidirectional"))
    )
    (net (code "115") (name "Net-(SENSORB-CMDP_COMP)") (class "Default")
      (node (ref "C28") (pin "2") (pinfunction "2_2") (pintype "passive"))
      (node (ref "SENSOR") (pin "H3") (pinfunction "CMDP_COMP_H3") (pintype "bidirectional"))
    )
    (net (code "116") (name "Net-(SENSORB-CMDP_COMP_INV)") (class "Default")
      (node (ref "C27") (pin "2") (pinfunction "2_2") (pintype "passive"))
      (node (ref "SENSOR") (pin "F3") (pinfunction "CMDP_COMP_INV_F3") (pintype "bidirectional"))
    )
    (net (code "117") (name "Net-(SENSORB-CMD_COLAMP)") (class "Default")
      (node (ref "C25") (pin "2") (pinfunction "2_2") (pintype "passive"))
      (node (ref "SENSOR") (pin "C6") (pinfunction "CMD_COLAMP_C6") (pintype "bidirectional"))
    )
    (net (code "118") (name "Net-(SENSORB-CMD_COL_LOAD)") (class "Default")
      (node (ref "C23") (pin "2") (pinfunction "2_2") (pintype "passive"))
      (node (ref "SENSOR") (pin "B1") (pinfunction "CMD_COL_LOAD_B1") (pintype "bidirectional"))
    )
    (net (code "119") (name "Net-(SENSORB-CMD_COL_PC)") (class "Default")
      (node (ref "C26") (pin "2") (pinfunction "2_2") (pintype "passive"))
      (node (ref "SENSOR") (pin "D1") (pinfunction "CMD_COL_PC_D1") (pintype "bidirectional"))
    )
    (net (code "120") (name "Net-(SENSORB-CMD_LVDS)") (class "Default")
      (node (ref "C62") (pin "1") (pinfunction "1_1") (pintype "passive"))
      (node (ref "SENSOR") (pin "C1") (pinfunction "CMD_LVDS_C1") (pintype "bidirectional"))
    )
    (net (code "121") (name "Net-(SENSORB-CMD_RAMP)") (class "Default")
      (node (ref "C24") (pin "2") (pinfunction "2_2") (pintype "passive"))
      (node (ref "SENSOR") (pin "B29") (pinfunction "CMD_RAMP_B29") (pintype "bidirectional"))
    )
    (net (code "122") (name "Net-(SENSORB-VBGAP)") (class "Default")
      (node (ref "C64") (pin "1") (pinfunction "1_1") (pintype "passive"))
      (node (ref "SENSOR") (pin "C29") (pinfunction "VBGAP_C29") (pintype "bidirectional"))
    )
    (net (code "123") (name "Net-(SENSORB-VCLAMP)") (class "Default")
      (node (ref "C63") (pin "1") (pinfunction "1_1") (pintype "passive"))
      (node (ref "SENSOR") (pin "D4") (pinfunction "VCLAMP_D4") (pintype "bidirectional"))
    )
    (net (code "124") (name "Net-(SENSORB-VCLAMP_ADC)") (class "Default")
      (node (ref "C60") (pin "1") (pinfunction "1_1") (pintype "passive"))
      (node (ref "SENSOR") (pin "G2") (pinfunction "VCLAMP_ADC_G2") (pintype "bidirectional"))
    )
    (net (code "125") (name "Net-(SENSORB-VPCH_H)") (class "Default")
      (node (ref "C71") (pin "1") (pinfunction "1_1") (pintype "passive"))
      (node (ref "SENSOR") (pin "C4") (pinfunction "VPCH_H_C4") (pintype "bidirectional"))
    )
    (net (code "126") (name "Net-(SENSORB-VPCH_L)") (class "Default")
      (node (ref "C14") (pin "1") (pinfunction "1_1") (pintype "passive"))
      (node (ref "SENSOR") (pin "A4") (pinfunction "VPCH_L_A4") (pintype "bidirectional"))
    )
    (net (code "127") (name "Net-(SENSORB-VREF)") (class "Default")
      (node (ref "C29") (pin "1") (pinfunction "1_1") (pintype "passive"))
      (node (ref "SENSOR") (pin "A3") (pinfunction "VREF_A3") (pintype "bidirectional"))
    )
    (net (code "128") (name "Net-(SENSORB-VREF_ADC)") (class "Default")
      (node (ref "C30") (pin "1") (pinfunction "1_1") (pintype "passive"))
      (node (ref "SENSOR") (pin "B3") (pinfunction "VREF_ADC_B3") (pintype "bidirectional"))
    )
    (net (code "129") (name "Net-(SENSORB-VRES_L)") (class "Default")
      (node (ref "C15") (pin "1") (pinfunction "1_1") (pintype "passive"))
      (node (ref "SENSOR") (pin "D5") (pinfunction "VRES_L_D5") (pintype "bidirectional"))
    )
    (net (code "130") (name "Net-(SENSORB-VTF_LOW0)") (class "Default")
      (node (ref "C18") (pin "1") (pinfunction "1_1") (pintype "passive"))
      (node (ref "SENSOR") (pin "C5") (pinfunction "VTF_LOW0_C5") (pintype "bidirectional"))
    )
    (net (code "131") (name "Net-(SENSORB-VTF_LOW1)") (class "Default")
      (node (ref "C19") (pin "1") (pinfunction "1_1") (pintype "passive"))
      (node (ref "SENSOR") (pin "D6") (pinfunction "VTF_LOW1_D6") (pintype "bidirectional"))
    )
    (net (code "132") (name "Net-(SENSORB-VTF_LOW2)") (class "Default")
      (node (ref "C20") (pin "1") (pinfunction "1_1") (pintype "passive"))
      (node (ref "SENSOR") (pin "B30") (pinfunction "VTF_LOW2_B30") (pintype "bidirectional"))
    )
    (net (code "133") (name "Net-(SENSORB-VTF_LOW3)") (class "Default")
      (node (ref "C21") (pin "1") (pinfunction "1_1") (pintype "passive"))
      (node (ref "SENSOR") (pin "C30") (pinfunction "VTF_LOW3_C30") (pintype "bidirectional"))
    )
    (net (code "134") (name "Net-(U3-ADJ)") (class "Default")
      (node (ref "R21") (pin "1") (pinfunction "1_1") (pintype "passive"))
      (node (ref "R22") (pin "2") (pinfunction "2_2") (pintype "passive"))
      (node (ref "U3") (pin "5") (pinfunction "ADJ_5") (pintype "input"))
    )
    (net (code "135") (name "Net-(U6-B4)") (class "Default")
      (node (ref "TP9") (pin "TP") (pinfunction "TP_TP") (pintype "input"))
      (node (ref "U6") (pin "9") (pinfunction "B4_9") (pintype "bidirectional"))
    )
    (net (code "136") (name "Net-(UEP-WP)") (class "Default")
      (node (ref "R1X") (pin "2") (pinfunction "2_2") (pintype "passive"))
      (node (ref "R2X") (pin "1") (pinfunction "1_1") (pintype "passive"))
      (node (ref "UEP") (pin "7") (pinfunction "WP_7") (pintype "input"))
    )
    (net (code "137") (name "Net-(UNE-VINA+)") (class "Default")
      (node (ref "R7") (pin "2") (pinfunction "2_2") (pintype "passive"))
      (node (ref "R8") (pin "1") (pinfunction "1_1") (pintype "passive"))
      (node (ref "UNE") (pin "3") (pinfunction "VINA+_3") (pintype "input"))
    )
    (net (code "138") (name "Net-(UNE-VINB-)") (class "Default")
      (node (ref "R8") (pin "2") (pinfunction "2_2") (pintype "passive"))
      (node (ref "R9") (pin "1") (pinfunction "1_1") (pintype "passive"))
      (node (ref "UNE") (pin "6") (pinfunction "VINB-_6") (pintype "input"))
    )
    (net (code "139") (name "Net-(UNN-VINA+)") (class "Default")
      (node (ref "R4") (pin "2") (pinfunction "2_2") (pintype "passive"))
      (node (ref "R5") (pin "1") (pinfunction "1_1") (pintype "passive"))
      (node (ref "UNN") (pin "3") (pinfunction "VINA+_3") (pintype "input"))
    )
    (net (code "140") (name "Net-(UNN-VINB-)") (class "Default")
      (node (ref "R5") (pin "2") (pinfunction "2_2") (pintype "passive"))
      (node (ref "R6") (pin "1") (pinfunction "1_1") (pintype "passive"))
      (node (ref "UNN") (pin "6") (pinfunction "VINB-_6") (pintype "input"))
    )
    (net (code "141") (name "Net-(UNW-VINA+)") (class "Default")
      (node (ref "R1") (pin "2") (pinfunction "2_2") (pintype "passive"))
      (node (ref "R2") (pin "1") (pinfunction "1_1") (pintype "passive"))
      (node (ref "UNW") (pin "3") (pinfunction "VINA+_3") (pintype "input"))
    )
    (net (code "142") (name "Net-(UNW-VINB-)") (class "Default")
      (node (ref "R2") (pin "2") (pinfunction "2_2") (pintype "passive"))
      (node (ref "R3") (pin "1") (pinfunction "1_1") (pintype "passive"))
      (node (ref "UNW") (pin "6") (pinfunction "VINB-_6") (pintype "input"))
    )
    (net (code "143") (name "Net-(USE-VINA+)") (class "Default")
      (node (ref "R10") (pin "2") (pinfunction "2_2") (pintype "passive"))
      (node (ref "R11") (pin "1") (pinfunction "1_1") (pintype "passive"))
      (node (ref "USE") (pin "3") (pinfunction "VINA+_3") (pintype "input"))
    )
    (net (code "144") (name "Net-(USE-VINB-)") (class "Default")
      (node (ref "R11") (pin "2") (pinfunction "2_2") (pintype "passive"))
      (node (ref "R12") (pin "1") (pinfunction "1_1") (pintype "passive"))
      (node (ref "USE") (pin "6") (pinfunction "VINB-_6") (pintype "input"))
    )
    (net (code "145") (name "Net-(USS-VINA+)") (class "Default")
      (node (ref "R13") (pin "2") (pinfunction "2_2") (pintype "passive"))
      (node (ref "R14") (pin "1") (pinfunction "1_1") (pintype "passive"))
      (node (ref "USS") (pin "3") (pinfunction "VINA+_3") (pintype "input"))
    )
    (net (code "146") (name "Net-(USS-VINB-)") (class "Default")
      (node (ref "R14") (pin "2") (pinfunction "2_2") (pintype "passive"))
      (node (ref "R15") (pin "1") (pinfunction "1_1") (pintype "passive"))
      (node (ref "USS") (pin "6") (pinfunction "VINB-_6") (pintype "input"))
    )
    (net (code "147") (name "Net-(USW-VINA+)") (class "Default")
      (node (ref "R16") (pin "2") (pinfunction "2_2") (pintype "passive"))
      (node (ref "R17") (pin "1") (pinfunction "1_1") (pintype "passive"))
      (node (ref "USW") (pin "3") (pinfunction "VINA+_3") (pintype "input"))
    )
    (net (code "148") (name "Net-(USW-VINB-)") (class "Default")
      (node (ref "R17") (pin "2") (pinfunction "2_2") (pintype "passive"))
      (node (ref "R18") (pin "1") (pinfunction "1_1") (pintype "passive"))
      (node (ref "USW") (pin "6") (pinfunction "VINB-_6") (pintype "input"))
    )
    (net (code "149") (name "S00_N") (class "Default")
      (node (ref "X-SOUTH") (pin "16") (pinfunction "16_16") (pintype "bidirectional"))
    )
    (net (code "150") (name "S00_P") (class "Default")
      (node (ref "X-SOUTH") (pin "14") (pinfunction "14_14") (pintype "bidirectional"))
    )
    (net (code "151") (name "S01_N") (class "Default")
      (node (ref "X-SOUTH") (pin "17") (pinfunction "17_17") (pintype "bidirectional"))
    )
    (net (code "152") (name "S01_P") (class "Default")
      (node (ref "X-SOUTH") (pin "15") (pinfunction "15_15") (pintype "bidirectional"))
    )
    (net (code "153") (name "S02_N") (class "Default")
      (node (ref "X-SOUTH") (pin "22") (pinfunction "22_22") (pintype "bidirectional"))
    )
    (net (code "154") (name "S02_P") (class "Default")
      (node (ref "X-SOUTH") (pin "20") (pinfunction "20_20") (pintype "bidirectional"))
    )
    (net (code "155") (name "S03_N") (class "Default")
      (node (ref "X-SOUTH") (pin "23") (pinfunction "23_23") (pintype "bidirectional"))
    )
    (net (code "156") (name "S03_P") (class "Default")
      (node (ref "X-SOUTH") (pin "21") (pinfunction "21_21") (pintype "bidirectional"))
    )
    (net (code "157") (name "S04_N") (class "Default")
      (node (ref "SENSOR") (pin "C24") (pinfunction "OUT32_N_C24") (pintype "output"))
      (node (ref "X-SOUTH") (pin "28") (pinfunction "28_28") (pintype "bidirectional"))
    )
    (net (code "158") (name "S04_P") (class "Default")
      (node (ref "SENSOR") (pin "C25") (pinfunction "OUT32_P_C25") (pintype "output"))
      (node (ref "X-SOUTH") (pin "26") (pinfunction "26_26") (pintype "bidirectional"))
    )
    (net (code "159") (name "S05_N") (class "Default")
      (node (ref "X-SOUTH") (pin "29") (pinfunction "29_29") (pintype "bidirectional"))
    )
    (net (code "160") (name "S05_P") (class "Default")
      (node (ref "X-SOUTH") (pin "27") (pinfunction "27_27") (pintype "bidirectional"))
    )
    (net (code "161") (name "S06_N") (class "Default")
      (node (ref "SENSOR") (pin "D23") (pinfunction "OUT30_N_D23") (pintype "output"))
      (node (ref "X-SOUTH") (pin "34") (pinfunction "34_34") (pintype "bidirectional"))
    )
    (net (code "162") (name "S06_P") (class "Default")
      (node (ref "SENSOR") (pin "D24") (pinfunction "OUT30_P_D24") (pintype "output"))
      (node (ref "X-SOUTH") (pin "32") (pinfunction "32_32") (pintype "bidirectional"))
    )
    (net (code "163") (name "S07_N") (class "Default")
      (node (ref "SENSOR") (pin "B24") (pinfunction "OUT31_N_B24") (pintype "output"))
      (node (ref "X-SOUTH") (pin "35") (pinfunction "35_35") (pintype "bidirectional"))
    )
    (net (code "164") (name "S07_P") (class "Default")
      (node (ref "SENSOR") (pin "B25") (pinfunction "OUT31_P_B25") (pintype "output"))
      (node (ref "X-SOUTH") (pin "33") (pinfunction "33_33") (pintype "bidirectional"))
    )
    (net (code "165") (name "S08_N") (class "Default")
      (node (ref "SENSOR") (pin "D21") (pinfunction "OUT27_N_D21") (pintype "output"))
      (node (ref "X-SOUTH") (pin "40") (pinfunction "40_40") (pintype "bidirectional"))
    )
    (net (code "166") (name "S08_P") (class "Default")
      (node (ref "SENSOR") (pin "D22") (pinfunction "OUT27_P_D22") (pintype "output"))
      (node (ref "X-SOUTH") (pin "38") (pinfunction "38_38") (pintype "bidirectional"))
    )
    (net (code "167") (name "S09_N") (class "Default")
      (node (ref "SENSOR") (pin "A23") (pinfunction "OUT29_N_A23") (pintype "output"))
      (node (ref "X-SOUTH") (pin "41") (pinfunction "41_41") (pintype "bidirectional"))
    )
    (net (code "168") (name "S09_P") (class "Default")
      (node (ref "SENSOR") (pin "A24") (pinfunction "OUT29_P_A24") (pintype "output"))
      (node (ref "X-SOUTH") (pin "39") (pinfunction "39_39") (pintype "bidirectional"))
    )
    (net (code "169") (name "S10_N") (class "Default")
      (node (ref "SENSOR") (pin "C21") (pinfunction "OUT28_N_C21") (pintype "output"))
      (node (ref "X-SOUTH") (pin "46") (pinfunction "46_46") (pintype "bidirectional"))
    )
    (net (code "170") (name "S10_P") (class "Default")
      (node (ref "SENSOR") (pin "C22") (pinfunction "OUT28_P_C22") (pintype "output"))
      (node (ref "X-SOUTH") (pin "44") (pinfunction "44_44") (pintype "bidirectional"))
    )
    (net (code "171") (name "S11_N") (class "Default")
      (node (ref "SENSOR") (pin "B20") (pinfunction "OUT26_N_B20") (pintype "output"))
      (node (ref "X-SOUTH") (pin "47") (pinfunction "47_47") (pintype "bidirectional"))
    )
    (net (code "172") (name "S11_P") (class "Default")
      (node (ref "SENSOR") (pin "B21") (pinfunction "OUT26_P_B21") (pintype "output"))
      (node (ref "X-SOUTH") (pin "45") (pinfunction "45_45") (pintype "bidirectional"))
    )
    (net (code "173") (name "S12_N") (class "Default")
      (node (ref "SENSOR") (pin "D19") (pinfunction "OUT24_N_D19") (pintype "output"))
      (node (ref "X-SOUTH") (pin "52") (pinfunction "52_52") (pintype "bidirectional"))
    )
    (net (code "174") (name "S12_P") (class "Default")
      (node (ref "SENSOR") (pin "D20") (pinfunction "OUT24_P_D20") (pintype "output"))
      (node (ref "X-SOUTH") (pin "50") (pinfunction "50_50") (pintype "bidirectional"))
    )
    (net (code "175") (name "S13_N") (class "Default")
      (node (ref "SENSOR") (pin "A19") (pinfunction "OUT23_N_A19") (pintype "output"))
      (node (ref "X-SOUTH") (pin "53") (pinfunction "53_53") (pintype "bidirectional"))
    )
    (net (code "176") (name "S13_P") (class "Default")
      (node (ref "SENSOR") (pin "A20") (pinfunction "OUT23_P_A20") (pintype "output"))
      (node (ref "X-SOUTH") (pin "51") (pinfunction "51_51") (pintype "bidirectional"))
    )
    (net (code "177") (name "S14_N") (class "Default")
      (node (ref "SENSOR") (pin "C19") (pinfunction "OUT25_N_C19") (pintype "output"))
      (node (ref "X-SOUTH") (pin "58") (pinfunction "58_58") (pintype "bidirectional"))
    )
    (net (code "178") (name "S14_P") (class "Default")
      (node (ref "SENSOR") (pin "C20") (pinfunction "OUT25_P_C20") (pintype "output"))
      (node (ref "X-SOUTH") (pin "56") (pinfunction "56_56") (pintype "bidirectional"))
    )
    (net (code "179") (name "S15_N") (class "Default")
      (node (ref "SENSOR") (pin "B18") (pinfunction "OUT22_N_B18") (pintype "output"))
      (node (ref "X-SOUTH") (pin "59") (pinfunction "59_59") (pintype "bidirectional"))
    )
    (net (code "180") (name "S15_P") (class "Default")
      (node (ref "SENSOR") (pin "B19") (pinfunction "OUT22_P_B19") (pintype "output"))
      (node (ref "X-SOUTH") (pin "57") (pinfunction "57_57") (pintype "bidirectional"))
    )
    (net (code "181") (name "S16_N") (class "Default")
      (node (ref "SENSOR") (pin "C17") (pinfunction "OUT21_N_C17") (pintype "output"))
      (node (ref "X-SOUTH") (pin "64") (pinfunction "64_64") (pintype "bidirectional"))
    )
    (net (code "182") (name "S16_P") (class "Default")
      (node (ref "SENSOR") (pin "C18") (pinfunction "OUT21_P_C18") (pintype "output"))
      (node (ref "X-SOUTH") (pin "62") (pinfunction "62_62") (pintype "bidirectional"))
    )
    (net (code "183") (name "S17_N") (class "Default")
      (node (ref "SENSOR") (pin "A17") (pinfunction "OUT19_N_A17") (pintype "output"))
      (node (ref "X-SOUTH") (pin "65") (pinfunction "65_65") (pintype "bidirectional"))
    )
    (net (code "184") (name "S17_P") (class "Default")
      (node (ref "SENSOR") (pin "A18") (pinfunction "OUT19_P_A18") (pintype "output"))
      (node (ref "X-SOUTH") (pin "63") (pinfunction "63_63") (pintype "bidirectional"))
    )
    (net (code "185") (name "S18_N") (class "Default")
      (node (ref "SENSOR") (pin "D17") (pinfunction "OUT20_N_D17") (pintype "output"))
      (node (ref "X-SOUTH") (pin "70") (pinfunction "70_70") (pintype "bidirectional"))
    )
    (net (code "186") (name "S18_P") (class "Default")
      (node (ref "SENSOR") (pin "D18") (pinfunction "OUT20_P_D18") (pintype "output"))
      (node (ref "X-SOUTH") (pin "68") (pinfunction "68_68") (pintype "bidirectional"))
    )
    (net (code "187") (name "S19_N") (class "Default")
      (node (ref "SENSOR") (pin "B16") (pinfunction "OUT18_N_B16") (pintype "output"))
      (node (ref "X-SOUTH") (pin "71") (pinfunction "71_71") (pintype "bidirectional"))
    )
    (net (code "188") (name "S19_P") (class "Default")
      (node (ref "SENSOR") (pin "B17") (pinfunction "OUT18_P_B17") (pintype "output"))
      (node (ref "X-SOUTH") (pin "69") (pinfunction "69_69") (pintype "bidirectional"))
    )
    (net (code "189") (name "S20_N") (class "Default")
      (node (ref "SENSOR") (pin "D15") (pinfunction "OUT17_N_D15") (pintype "output"))
      (node (ref "X-SOUTH") (pin "76") (pinfunction "76_76") (pintype "bidirectional"))
    )
    (net (code "190") (name "S20_P") (class "Default")
      (node (ref "SENSOR") (pin "D16") (pinfunction "OUT17_P_D16") (pintype "output"))
      (node (ref "X-SOUTH") (pin "74") (pinfunction "74_74") (pintype "bidirectional"))
    )
    (net (code "191") (name "S21_N") (class "Default")
      (node (ref "SENSOR") (pin "B14") (pinfunction "OUT16_N_B14") (pintype "output"))
      (node (ref "X-SOUTH") (pin "77") (pinfunction "77_77") (pintype "bidirectional"))
    )
    (net (code "192") (name "S21_P") (class "Default")
      (node (ref "SENSOR") (pin "B15") (pinfunction "OUT16_P_B15") (pintype "output"))
      (node (ref "X-SOUTH") (pin "75") (pinfunction "75_75") (pintype "bidirectional"))
    )
    (net (code "193") (name "S22_N") (class "Default")
      (node (ref "SENSOR") (pin "D13") (pinfunction "OUT15_N_D13") (pintype "output"))
      (node (ref "X-SOUTH") (pin "82") (pinfunction "82_82") (pintype "bidirectional"))
    )
    (net (code "194") (name "S22_P") (class "Default")
      (node (ref "SENSOR") (pin "D14") (pinfunction "OUT15_P_D14") (pintype "output"))
      (node (ref "X-SOUTH") (pin "80") (pinfunction "80_80") (pintype "bidirectional"))
    )
    (net (code "195") (name "S23_N") (class "Default")
      (node (ref "SENSOR") (pin "A13") (pinfunction "OUT13_N_A13") (pintype "output"))
      (node (ref "X-SOUTH") (pin "83") (pinfunction "83_83") (pintype "bidirectional"))
    )
    (net (code "196") (name "S23_P") (class "Default")
      (node (ref "SENSOR") (pin "A14") (pinfunction "OUT13_P_A14") (pintype "output"))
      (node (ref "X-SOUTH") (pin "81") (pinfunction "81_81") (pintype "bidirectional"))
    )
    (net (code "197") (name "S24_N") (class "Default")
      (node (ref "SENSOR") (pin "C13") (pinfunction "OUT14_N_C13") (pintype "output"))
      (node (ref "X-SOUTH") (pin "88") (pinfunction "88_88") (pintype "bidirectional"))
    )
    (net (code "198") (name "S24_P") (class "Default")
      (node (ref "SENSOR") (pin "C14") (pinfunction "OUT14_P_C14") (pintype "output"))
      (node (ref "X-SOUTH") (pin "86") (pinfunction "86_86") (pintype "bidirectional"))
    )
    (net (code "199") (name "S25_N") (class "Default")
      (node (ref "SENSOR") (pin "B12") (pinfunction "OUT12_N_B12") (pintype "output"))
      (node (ref "X-SOUTH") (pin "89") (pinfunction "89_89") (pintype "bidirectional"))
    )
    (net (code "200") (name "S25_P") (class "Default")
      (node (ref "SENSOR") (pin "B13") (pinfunction "OUT12_P_B13") (pintype "output"))
      (node (ref "X-SOUTH") (pin "87") (pinfunction "87_87") (pintype "bidirectional"))
    )
    (net (code "201") (name "S26_N") (class "Default")
      (node (ref "SENSOR") (pin "D11") (pinfunction "OUT10_N_D11") (pintype "output"))
      (node (ref "X-SOUTH") (pin "94") (pinfunction "94_94") (pintype "bidirectional"))
    )
    (net (code "202") (name "S26_P") (class "Default")
      (node (ref "SENSOR") (pin "D12") (pinfunction "OUT10_P_D12") (pintype "output"))
      (node (ref "X-SOUTH") (pin "92") (pinfunction "92_92") (pintype "bidirectional"))
    )
    (net (code "203") (name "S27_N") (class "Default")
      (node (ref "SENSOR") (pin "A11") (pinfunction "OUT9_N_A11") (pintype "output"))
      (node (ref "X-SOUTH") (pin "95") (pinfunction "95_95") (pintype "bidirectional"))
    )
    (net (code "204") (name "S27_P") (class "Default")
      (node (ref "SENSOR") (pin "A12") (pinfunction "OUT9_P_A12") (pintype "output"))
      (node (ref "X-SOUTH") (pin "93") (pinfunction "93_93") (pintype "bidirectional"))
    )
    (net (code "205") (name "S28_N") (class "Default")
      (node (ref "SENSOR") (pin "C11") (pinfunction "OUT11_N_C11") (pintype "output"))
      (node (ref "X-SOUTH") (pin "100") (pinfunction "100_100") (pintype "bidirectional"))
    )
    (net (code "206") (name "S28_P") (class "Default")
      (node (ref "SENSOR") (pin "C12") (pinfunction "OUT11_P_C12") (pintype "output"))
      (node (ref "X-SOUTH") (pin "98") (pinfunction "98_98") (pintype "bidirectional"))
    )
    (net (code "207") (name "S29_N") (class "Default")
      (node (ref "SENSOR") (pin "B10") (pinfunction "OUT8_N_B10") (pintype "output"))
      (node (ref "X-SOUTH") (pin "101") (pinfunction "101_101") (pintype "bidirectional"))
    )
    (net (code "208") (name "S29_P") (class "Default")
      (node (ref "SENSOR") (pin "B11") (pinfunction "OUT8_P_B11") (pintype "output"))
      (node (ref "X-SOUTH") (pin "99") (pinfunction "99_99") (pintype "bidirectional"))
    )
    (net (code "209") (name "S30_N") (class "Default")
      (node (ref "SENSOR") (pin "C9") (pinfunction "OUT7_N_C9") (pintype "output"))
      (node (ref "X-SOUTH") (pin "106") (pinfunction "106_106") (pintype "bidirectional"))
    )
    (net (code "210") (name "S30_P") (class "Default")
      (node (ref "SENSOR") (pin "C10") (pinfunction "OUT7_P_C10") (pintype "output"))
      (node (ref "X-SOUTH") (pin "104") (pinfunction "104_104") (pintype "bidirectional"))
    )
    (net (code "211") (name "S31_N") (class "Default")
      (node (ref "SENSOR") (pin "B8") (pinfunction "OUT5_N_B8") (pintype "output"))
      (node (ref "X-SOUTH") (pin "107") (pinfunction "107_107") (pintype "bidirectional"))
    )
    (net (code "212") (name "S31_P") (class "Default")
      (node (ref "SENSOR") (pin "B9") (pinfunction "OUT5_P_B9") (pintype "output"))
      (node (ref "X-SOUTH") (pin "105") (pinfunction "105_105") (pintype "bidirectional"))
    )
    (net (code "213") (name "S32_N") (class "Default")
      (node (ref "SENSOR") (pin "D9") (pinfunction "OUT6_N_D9") (pintype "output"))
      (node (ref "X-SOUTH") (pin "112") (pinfunction "112_112") (pintype "bidirectional"))
    )
    (net (code "214") (name "S32_P") (class "Default")
      (node (ref "SENSOR") (pin "D10") (pinfunction "OUT6_P_D10") (pintype "output"))
      (node (ref "X-SOUTH") (pin "110") (pinfunction "110_110") (pintype "bidirectional"))
    )
    (net (code "215") (name "S33_N") (class "Default")
      (node (ref "SENSOR") (pin "A7") (pinfunction "OUT2_N_A7") (pintype "output"))
      (node (ref "X-SOUTH") (pin "113") (pinfunction "113_113") (pintype "bidirectional"))
    )
    (net (code "216") (name "S33_P") (class "Default")
      (node (ref "SENSOR") (pin "A8") (pinfunction "OUT2_P_A8") (pintype "output"))
      (node (ref "X-SOUTH") (pin "111") (pinfunction "111_111") (pintype "bidirectional"))
    )
    (net (code "217") (name "S34_N") (class "Default")
      (node (ref "SENSOR") (pin "C7") (pinfunction "OUT4_N_C7") (pintype "output"))
      (node (ref "X-SOUTH") (pin "118") (pinfunction "118_118") (pintype "bidirectional"))
    )
    (net (code "218") (name "S34_P") (class "Default")
      (node (ref "SENSOR") (pin "C8") (pinfunction "OUT4_P_C8") (pintype "output"))
      (node (ref "X-SOUTH") (pin "116") (pinfunction "116_116") (pintype "bidirectional"))
    )
    (net (code "219") (name "S35_N") (class "Default")
      (node (ref "SENSOR") (pin "B6") (pinfunction "OUT1_N_B6") (pintype "output"))
      (node (ref "X-SOUTH") (pin "119") (pinfunction "119_119") (pintype "bidirectional"))
    )
    (net (code "220") (name "S35_P") (class "Default")
      (node (ref "SENSOR") (pin "B7") (pinfunction "OUT1_P_B7") (pintype "output"))
      (node (ref "X-SOUTH") (pin "117") (pinfunction "117_117") (pintype "bidirectional"))
    )
    (net (code "221") (name "S36_N") (class "Default")
      (node (ref "SENSOR") (pin "D7") (pinfunction "OUT3_N_D7") (pintype "output"))
      (node (ref "X-SOUTH") (pin "124") (pinfunction "124_124") (pintype "bidirectional"))
    )
    (net (code "222") (name "S36_P") (class "Default")
      (node (ref "SENSOR") (pin "D8") (pinfunction "OUT3_P_D8") (pintype "output"))
      (node (ref "X-SOUTH") (pin "122") (pinfunction "122_122") (pintype "bidirectional"))
    )
    (net (code "223") (name "S37_N") (class "Default")
      (node (ref "SENSOR") (pin "A5") (pinfunction "OUTCTR_N_A5") (pintype "output"))
      (node (ref "X-SOUTH") (pin "125") (pinfunction "125_125") (pintype "bidirectional"))
    )
    (net (code "224") (name "S37_P") (class "Default")
      (node (ref "SENSOR") (pin "A6") (pinfunction "OUTCTR_P_A6") (pintype "output"))
      (node (ref "X-SOUTH") (pin "123") (pinfunction "123_123") (pintype "bidirectional"))
    )
    (net (code "225") (name "S38_N") (class "Default")
      (node (ref "X-SOUTH") (pin "130") (pinfunction "130_130") (pintype "bidirectional"))
    )
    (net (code "226") (name "S38_P") (class "Default")
      (node (ref "X-SOUTH") (pin "128") (pinfunction "128_128") (pintype "bidirectional"))
    )
    (net (code "227") (name "S39_N") (class "Default")
      (node (ref "U3") (pin "6") (pinfunction "EN_6") (pintype "input"))
      (node (ref "X-SOUTH") (pin "131") (pinfunction "131_131") (pintype "bidirectional"))
    )
    (net (code "228") (name "S39_P") (class "Default")
      (node (ref "X-SOUTH") (pin "129") (pinfunction "129_129") (pintype "bidirectional"))
    )
    (net (code "229") (name "SPI_CLK") (class "Default")
      (node (ref "SENSOR") (pin "H29") (pinfunction "SPI_CLK_H29") (pintype "input"))
      (node (ref "U4") (pin "11") (pinfunction "B2_11") (pintype "bidirectional"))
    )
    (net (code "230") (name "SPI_EN") (class "Default")
      (node (ref "SENSOR") (pin "F28") (pinfunction "SPI_EN_F28") (pintype "input"))
      (node (ref "U4") (pin "9") (pinfunction "B4_9") (pintype "bidirectional"))
    )
    (net (code "231") (name "SPI_IN") (class "Default")
      (node (ref "SENSOR") (pin "E28") (pinfunction "SPI_IN_E28") (pintype "input"))
      (node (ref "U4") (pin "12") (pinfunction "B1_12") (pintype "bidirectional"))
    )
    (net (code "232") (name "SPI_OUT") (class "Default")
      (node (ref "SENSOR") (pin "G28") (pinfunction "SPI_OUT_G28") (pintype "output"))
      (node (ref "U4") (pin "10") (pinfunction "B3_10") (pintype "bidirectional"))
    )
    (net (code "233") (name "SYS_RES_N") (class "Default")
      (node (ref "SENSOR") (pin "F30") (pinfunction "SYS_RES_N_F30") (pintype "input"))
      (node (ref "U5") (pin "10") (pinfunction "B3_10") (pintype "bidirectional"))
    )
    (net (code "234") (name "S_CHK_EN") (class "Default")
      (node (ref "X-SOUTH") (pin "8") (pinfunction "8_8") (pintype "bidirectional"))
    )
    (net (code "235") (name "S_CHK_V") (class "Default")
      (node (ref "C5") (pin "1") (pinfunction "1_1") (pintype "passive"))
      (node (ref "C6") (pin "1") (pinfunction "1_1") (pintype "passive"))
      (node (ref "C7") (pin "1") (pinfunction "1_1") (pintype "passive"))
      (node (ref "R20") (pin "1") (pinfunction "1_1") (pintype "passive"))
      (node (ref "TP3") (pin "TP") (pinfunction "TP_TP") (pintype "input"))
      (node (ref "USE") (pin "8") (pinfunction "VDD_8") (pintype "power_in"))
      (node (ref "USS") (pin "8") (pinfunction "VDD_8") (pintype "power_in"))
      (node (ref "USW") (pin "8") (pinfunction "VDD_8") (pintype "power_in"))
      (node (ref "X-SOUTH") (pin "10") (pinfunction "10_10") (pintype "bidirectional"))
    )
    (net (code "236") (name "S_I2C_EN") (class "Default")
      (node (ref "X-SOUTH") (pin "137") (pinfunction "137_137") (pintype "bidirectional"))
    )
    (net (code "237") (name "S_I2C_V") (class "Default")
      (node (ref "U7") (pin "8") (pinfunction "VCC_8") (pintype "power_in"))
      (node (ref "X-SOUTH") (pin "135") (pinfunction "135_135") (pintype "bidirectional"))
    )
    (net (code "238") (name "S_REF") (class "Default")
      (node (ref "R20") (pin "2") (pinfunction "2_2") (pintype "passive"))
      (node (ref "TP4") (pin "TP") (pinfunction "TP_TP") (pintype "input"))
      (node (ref "U2") (pin "1") (pinfunction "CATHODE_1") (pintype "output"))
      (node (ref "U2") (pin "3") (pinfunction "REF_3") (pintype "input"))
      (node (ref "USE") (pin "2") (pinfunction "VINA-_2") (pintype "input"))
      (node (ref "USE") (pin "5") (pinfunction "VINB+_5") (pintype "input"))
      (node (ref "USS") (pin "2") (pinfunction "VINA-_2") (pintype "input"))
      (node (ref "USS") (pin "5") (pinfunction "VINB+_5") (pintype "input"))
      (node (ref "USW") (pin "2") (pinfunction "VINA-_2") (pintype "input"))
      (node (ref "USW") (pin "5") (pinfunction "VINB+_5") (pintype "input"))
    )
    (net (code "239") (name "S_SCK") (class "Default")
      (node (ref "X-SOUTH") (pin "144") (pinfunction "144_144") (pintype "bidirectional"))
    )
    (net (code "240") (name "S_SCL") (class "Default")
      (node (ref "U7") (pin "2") (pinfunction "SCL_2") (pintype "input"))
      (node (ref "X-SOUTH") (pin "143") (pinfunction "143_143") (pintype "bidirectional"))
    )
    (net (code "241") (name "S_SDA") (class "Default")
      (node (ref "U7") (pin "1") (pinfunction "SDA_1") (pintype "bidirectional"))
      (node (ref "X-SOUTH") (pin "141") (pinfunction "141_141") (pintype "bidirectional"))
    )
    (net (code "242") (name "S_SDI") (class "Default")
      (node (ref "X-SOUTH") (pin "140") (pinfunction "140_140") (pintype "bidirectional"))
    )
    (net (code "243") (name "S_SDO") (class "Default")
      (node (ref "X-SOUTH") (pin "142") (pinfunction "142_142") (pintype "bidirectional"))
    )
    (net (code "244") (name "S_SPI_EN") (class "Default")
      (node (ref "X-SOUTH") (pin "136") (pinfunction "136_136") (pintype "bidirectional"))
    )
    (net (code "245") (name "S_SPI_V") (class "Default")
      (node (ref "X-SOUTH") (pin "134") (pinfunction "134_134") (pintype "bidirectional"))
    )
    (net (code "246") (name "S_VE") (class "Default")
      (node (ref "X-SOUTH") (pin "13") (pinfunction "13_13") (pintype "bidirectional"))
      (node (ref "X-SOUTH") (pin "19") (pinfunction "19_19") (pintype "bidirectional"))
      (node (ref "X-SOUTH") (pin "25") (pinfunction "25_25") (pintype "bidirectional"))
      (node (ref "X-SOUTH") (pin "31") (pinfunction "31_31") (pintype "bidirectional"))
      (node (ref "X-SOUTH") (pin "37") (pinfunction "37_37") (pintype "bidirectional"))
    )
    (net (code "247") (name "S_VE_CV") (class "Default")
      (node (ref "C11") (pin "1") (pinfunction "1_1") (pintype "passive"))
      (node (ref "R10") (pin "1") (pinfunction "1_1") (pintype "passive"))
      (node (ref "X-SOUTH") (pin "2") (pinfunction "2_2") (pintype "bidirectional"))
    )
    (net (code "248") (name "S_VE_OV") (class "Default")
      (node (ref "USE") (pin "7") (pinfunction "OUTB_7") (pintype "output"))
      (node (ref "X-SOUTH") (pin "1") (pinfunction "1_1") (pintype "bidirectional"))
    )
    (net (code "249") (name "S_VE_UV") (class "Default")
      (node (ref "USE") (pin "1") (pinfunction "OUTA_1") (pintype "output"))
      (node (ref "X-SOUTH") (pin "7") (pinfunction "7_7") (pintype "bidirectional"))
    )
    (net (code "250") (name "S_VS") (class "Default")
      (node (ref "C45") (pin "1") (pinfunction "1_1") (pintype "passive"))
      (node (ref "C46") (pin "1") (pinfunction "1_1") (pintype "passive"))
      (node (ref "C47") (pin "1") (pinfunction "1_1") (pintype "passive"))
      (node (ref "C48") (pin "1") (pinfunction "1_1") (pintype "passive"))
      (node (ref "C49") (pin "1") (pinfunction "1_1") (pintype "passive"))
      (node (ref "C72") (pin "1") (pinfunction "1_1") (pintype "passive"))
      (node (ref "C73") (pin "1") (pinfunction "1_1") (pintype "passive"))
      (node (ref "C74") (pin "1") (pinfunction "1_1") (pintype "passive"))
      (node (ref "C81") (pin "1") (pinfunction "1_1") (pintype "passive"))
      (node (ref "C82") (pin "1") (pinfunction "1_1") (pintype "passive"))
      (node (ref "C83") (pin "1") (pinfunction "1_1") (pintype "passive"))
      (node (ref "SENSOR") (pin "A30") (pinfunction "VDD_PIX_A30") (pintype "power_in"))
      (node (ref "SENSOR") (pin "D28") (pinfunction "VDD_PIX_D28") (pintype "power_in"))
      (node (ref "SENSOR") (pin "D30") (pinfunction "VDD_PIX_D30") (pintype "power_in"))
      (node (ref "SENSOR") (pin "G1") (pinfunction "VDD_PIX_G1") (pintype "power_in"))
      (node (ref "SENSOR") (pin "H28") (pinfunction "VDD_PIX_H28") (pintype "power_in"))
      (node (ref "TP6") (pin "TP") (pinfunction "TP_TP") (pintype "input"))
      (node (ref "X-SOUTH") (pin "49") (pinfunction "49_49") (pintype "bidirectional"))
      (node (ref "X-SOUTH") (pin "55") (pinfunction "55_55") (pintype "bidirectional"))
      (node (ref "X-SOUTH") (pin "61") (pinfunction "61_61") (pintype "bidirectional"))
      (node (ref "X-SOUTH") (pin "67") (pinfunction "67_67") (pintype "bidirectional"))
      (node (ref "X-SOUTH") (pin "73") (pinfunction "73_73") (pintype "bidirectional"))
      (node (ref "X-SOUTH") (pin "79") (pinfunction "79_79") (pintype "bidirectional"))
      (node (ref "X-SOUTH") (pin "85") (pinfunction "85_85") (pintype "bidirectional"))
      (node (ref "X-SOUTH") (pin "91") (pinfunction "91_91") (pintype "bidirectional"))
      (node (ref "X-SOUTH") (pin "97") (pinfunction "97_97") (pintype "bidirectional"))
    )
    (net (code "251") (name "S_VS_CV") (class "Default")
      (node (ref "C12") (pin "1") (pinfunction "1_1") (pintype "passive"))
      (node (ref "R13") (pin "1") (pinfunction "1_1") (pintype "passive"))
      (node (ref "X-SOUTH") (pin "4") (pinfunction "4_4") (pintype "bidirectional"))
    )
    (net (code "252") (name "S_VS_OV") (class "Default")
      (node (ref "USS") (pin "7") (pinfunction "OUTB_7") (pintype "output"))
      (node (ref "X-SOUTH") (pin "3") (pinfunction "3_3") (pintype "bidirectional"))
    )
    (net (code "253") (name "S_VS_UV") (class "Default")
      (node (ref "USS") (pin "1") (pinfunction "OUTA_1") (pintype "output"))
      (node (ref "X-SOUTH") (pin "9") (pinfunction "9_9") (pintype "bidirectional"))
    )
    (net (code "254") (name "S_VW") (class "Default")
      (node (ref "C90") (pin "1") (pinfunction "1_1") (pintype "passive"))
      (node (ref "U3") (pin "1") (pinfunction "BIAS_1") (pintype "power_in"))
      (node (ref "U3") (pin "3") (pinfunction "IN_3") (pintype "power_in"))
      (node (ref "X-SOUTH") (pin "109") (pinfunction "109_109") (pintype "bidirectional"))
      (node (ref "X-SOUTH") (pin "115") (pinfunction "115_115") (pintype "bidirectional"))
      (node (ref "X-SOUTH") (pin "121") (pinfunction "121_121") (pintype "bidirectional"))
      (node (ref "X-SOUTH") (pin "127") (pinfunction "127_127") (pintype "bidirectional"))
      (node (ref "X-SOUTH") (pin "133") (pinfunction "133_133") (pintype "bidirectional"))
    )
    (net (code "255") (name "S_VW_CV") (class "Default")
      (node (ref "C13") (pin "1") (pinfunction "1_1") (pintype "passive"))
      (node (ref "R16") (pin "1") (pinfunction "1_1") (pintype "passive"))
      (node (ref "X-SOUTH") (pin "6") (pinfunction "6_6") (pintype "bidirectional"))
    )
    (net (code "256") (name "S_VW_OV") (class "Default")
      (node (ref "USW") (pin "7") (pinfunction "OUTB_7") (pintype "output"))
      (node (ref "X-SOUTH") (pin "5") (pinfunction "5_5") (pintype "bidirectional"))
    )
    (net (code "257") (name "S_VW_UV") (class "Default")
      (node (ref "USW") (pin "1") (pinfunction "OUTA_1") (pintype "output"))
      (node (ref "X-SOUTH") (pin "11") (pinfunction "11_11") (pintype "bidirectional"))
    )
    (net (code "258") (name "TDIG1") (class "Default")
      (node (ref "SENSOR") (pin "G27") (pinfunction "TDIG1_G27") (pintype "output"))
      (node (ref "U5") (pin "9") (pinfunction "B4_9") (pintype "bidirectional"))
    )
    (net (code "259") (name "TDIG2") (class "Default")
      (node (ref "SENSOR") (pin "G26") (pinfunction "TDIG2_G26") (pintype "output"))
      (node (ref "U6") (pin "11") (pinfunction "B2_11") (pintype "bidirectional"))
    )
    (net (code "260") (name "T_EXP1") (class "Default")
      (node (ref "SENSOR") (pin "H30") (pinfunction "T_EXP1_H30") (pintype "input"))
      (node (ref "U5") (pin "12") (pinfunction "B1_12") (pintype "bidirectional"))
    )
    (net (code "261") (name "T_EXP2") (class "Default")
      (node (ref "SENSOR") (pin "E29") (pinfunction "T_EXP2_E29") (pintype "input"))
      (node (ref "U6") (pin "10") (pinfunction "B3_10") (pintype "bidirectional"))
    )
    (net (code "262") (name "VRAMP1") (class "Default")
      (node (ref "C16") (pin "1") (pinfunction "1_1") (pintype "passive"))
      (node (ref "R23") (pin "1") (pinfunction "1_1") (pintype "passive"))
      (node (ref "SENSOR") (pin "G29") (pinfunction "VRAMP1_G29") (pintype "bidirectional"))
    )
    (net (code "263") (name "VRAMP2") (class "Default")
      (node (ref "C17") (pin "1") (pinfunction "1_1") (pintype "passive"))
      (node (ref "R23") (pin "2") (pinfunction "2_2") (pintype "passive"))
      (node (ref "SENSOR") (pin "F29") (pinfunction "VRAMP2_F29") (pintype "bidirectional"))
    )
    (net (code "264") (name "VTREF") (class "Default")
      (node (ref "C65") (pin "1") (pinfunction "1_1") (pintype "passive"))
      (node (ref "C91") (pin "2") (pinfunction "2_2") (pintype "passive"))
      (node (ref "R21") (pin "2") (pinfunction "2_2") (pintype "passive"))
      (node (ref "R24") (pin "1") (pinfunction "1_1") (pintype "passive"))
      (node (ref "SENSOR") (pin "B2") (pinfunction "VTREF_B2") (pintype "bidirectional"))
      (node (ref "U3") (pin "4") (pinfunction "OUT_4") (pintype "power_in"))
    )
    (net (code "265") (name "VTSIG") (class "Default")
      (node (ref "C66") (pin "1") (pinfunction "1_1") (pintype "passive"))
      (node (ref "R24") (pin "2") (pinfunction "2_2") (pintype "passive"))
      (node (ref "SENSOR") (pin "C2") (pinfunction "VTSIG_C2") (pintype "bidirectional"))
    )
    (net (code "266") (name "unconnected-(U1-NC-Pad2)") (class "Default")
      (node (ref "U1") (pin "2") (pinfunction "NC_2") (pintype "no_connect"))
    )
    (net (code "267") (name "unconnected-(U1-NC-Pad4)") (class "Default")
      (node (ref "U1") (pin "4") (pinfunction "NC_4") (pintype "no_connect"))
    )
    (net (code "268") (name "unconnected-(U1-NC-Pad5)") (class "Default")
      (node (ref "U1") (pin "5") (pinfunction "NC_5") (pintype "no_connect"))
    )
    (net (code "269") (name "unconnected-(U2-NC-Pad2)") (class "Default")
      (node (ref "U2") (pin "2") (pinfunction "NC_2") (pintype "no_connect"))
    )
    (net (code "270") (name "unconnected-(U2-NC-Pad4)") (class "Default")
      (node (ref "U2") (pin "4") (pinfunction "NC_4") (pintype "no_connect"))
    )
    (net (code "271") (name "unconnected-(U2-NC-Pad5)") (class "Default")
      (node (ref "U2") (pin "5") (pinfunction "NC_5") (pintype "no_connect"))
    )
    (net (code "272") (name "unconnected-(U7-OS-Pad3)") (class "Default")
      (node (ref "U7") (pin "3") (pinfunction "OS_3") (pintype "output"))
    )
    (net (code "273") (name "unconnected-(X-NORTH-PadM1)") (class "Default")
      (node (ref "X-NORTH") (pin "M1") (pinfunction "M1_M1") (pintype "bidirectional"))
    )
    (net (code "274") (name "unconnected-(X-NORTH-PadM2)") (class "Default")
      (node (ref "X-NORTH") (pin "M2") (pinfunction "M2_M2") (pintype "bidirectional"))
    )
    (net (code "275") (name "unconnected-(X-SOUTH-PadM1)") (class "Default")
      (node (ref "X-SOUTH") (pin "M1") (pinfunction "M1_M1") (pintype "bidirectional"))
    )
    (net (code "276") (name "unconnected-(X-SOUTH-PadM2)") (class "Default")
      (node (ref "X-SOUTH") (pin "M2") (pinfunction "M2_M2") (pintype "bidirectional"))
    )
  )
)
